# MAIN.net
KiCad netlist of a schematic drawn in Altium Designer
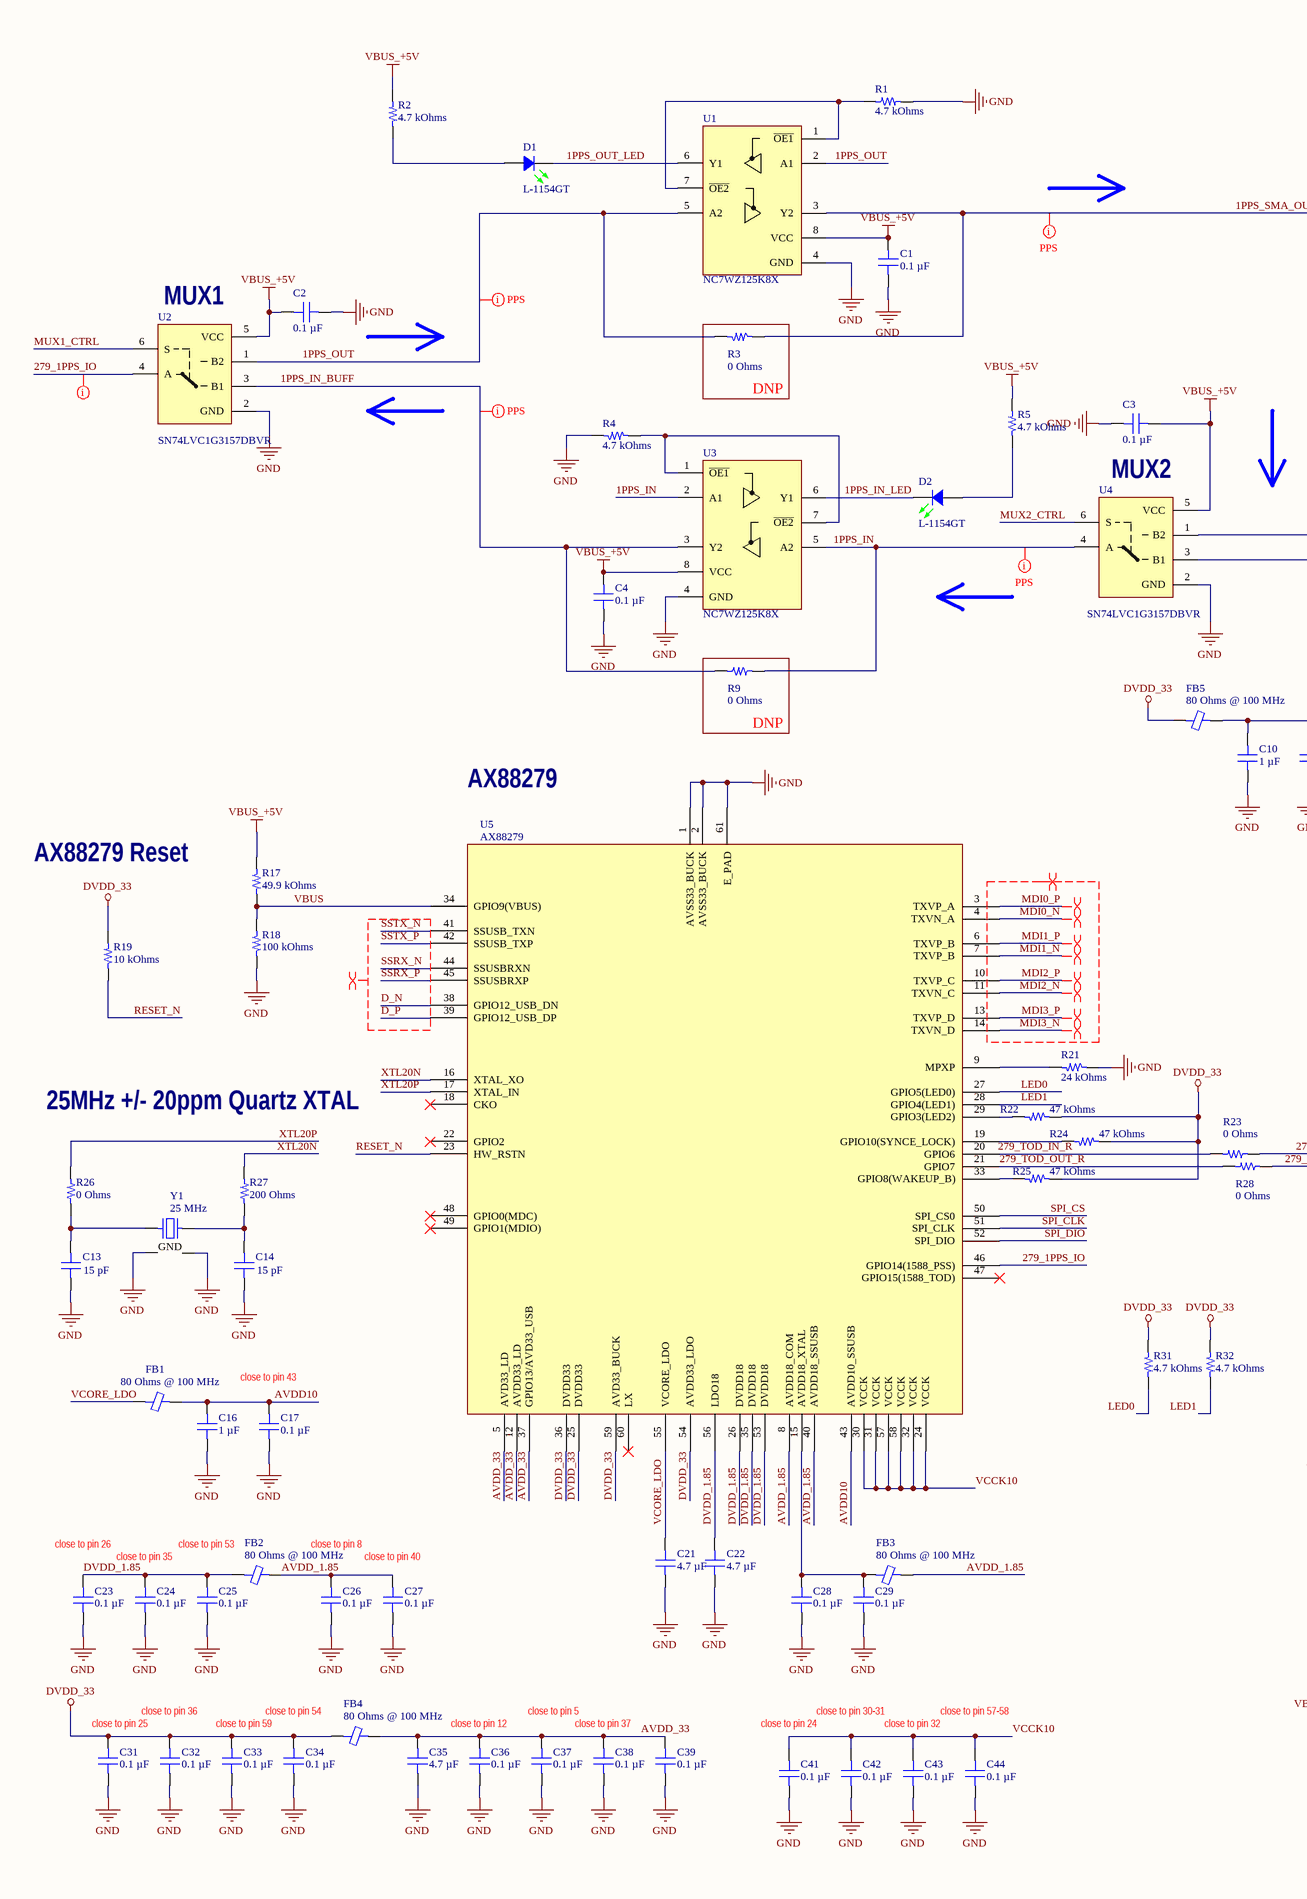
[diagram p0: MAIN.SchDoc, left]
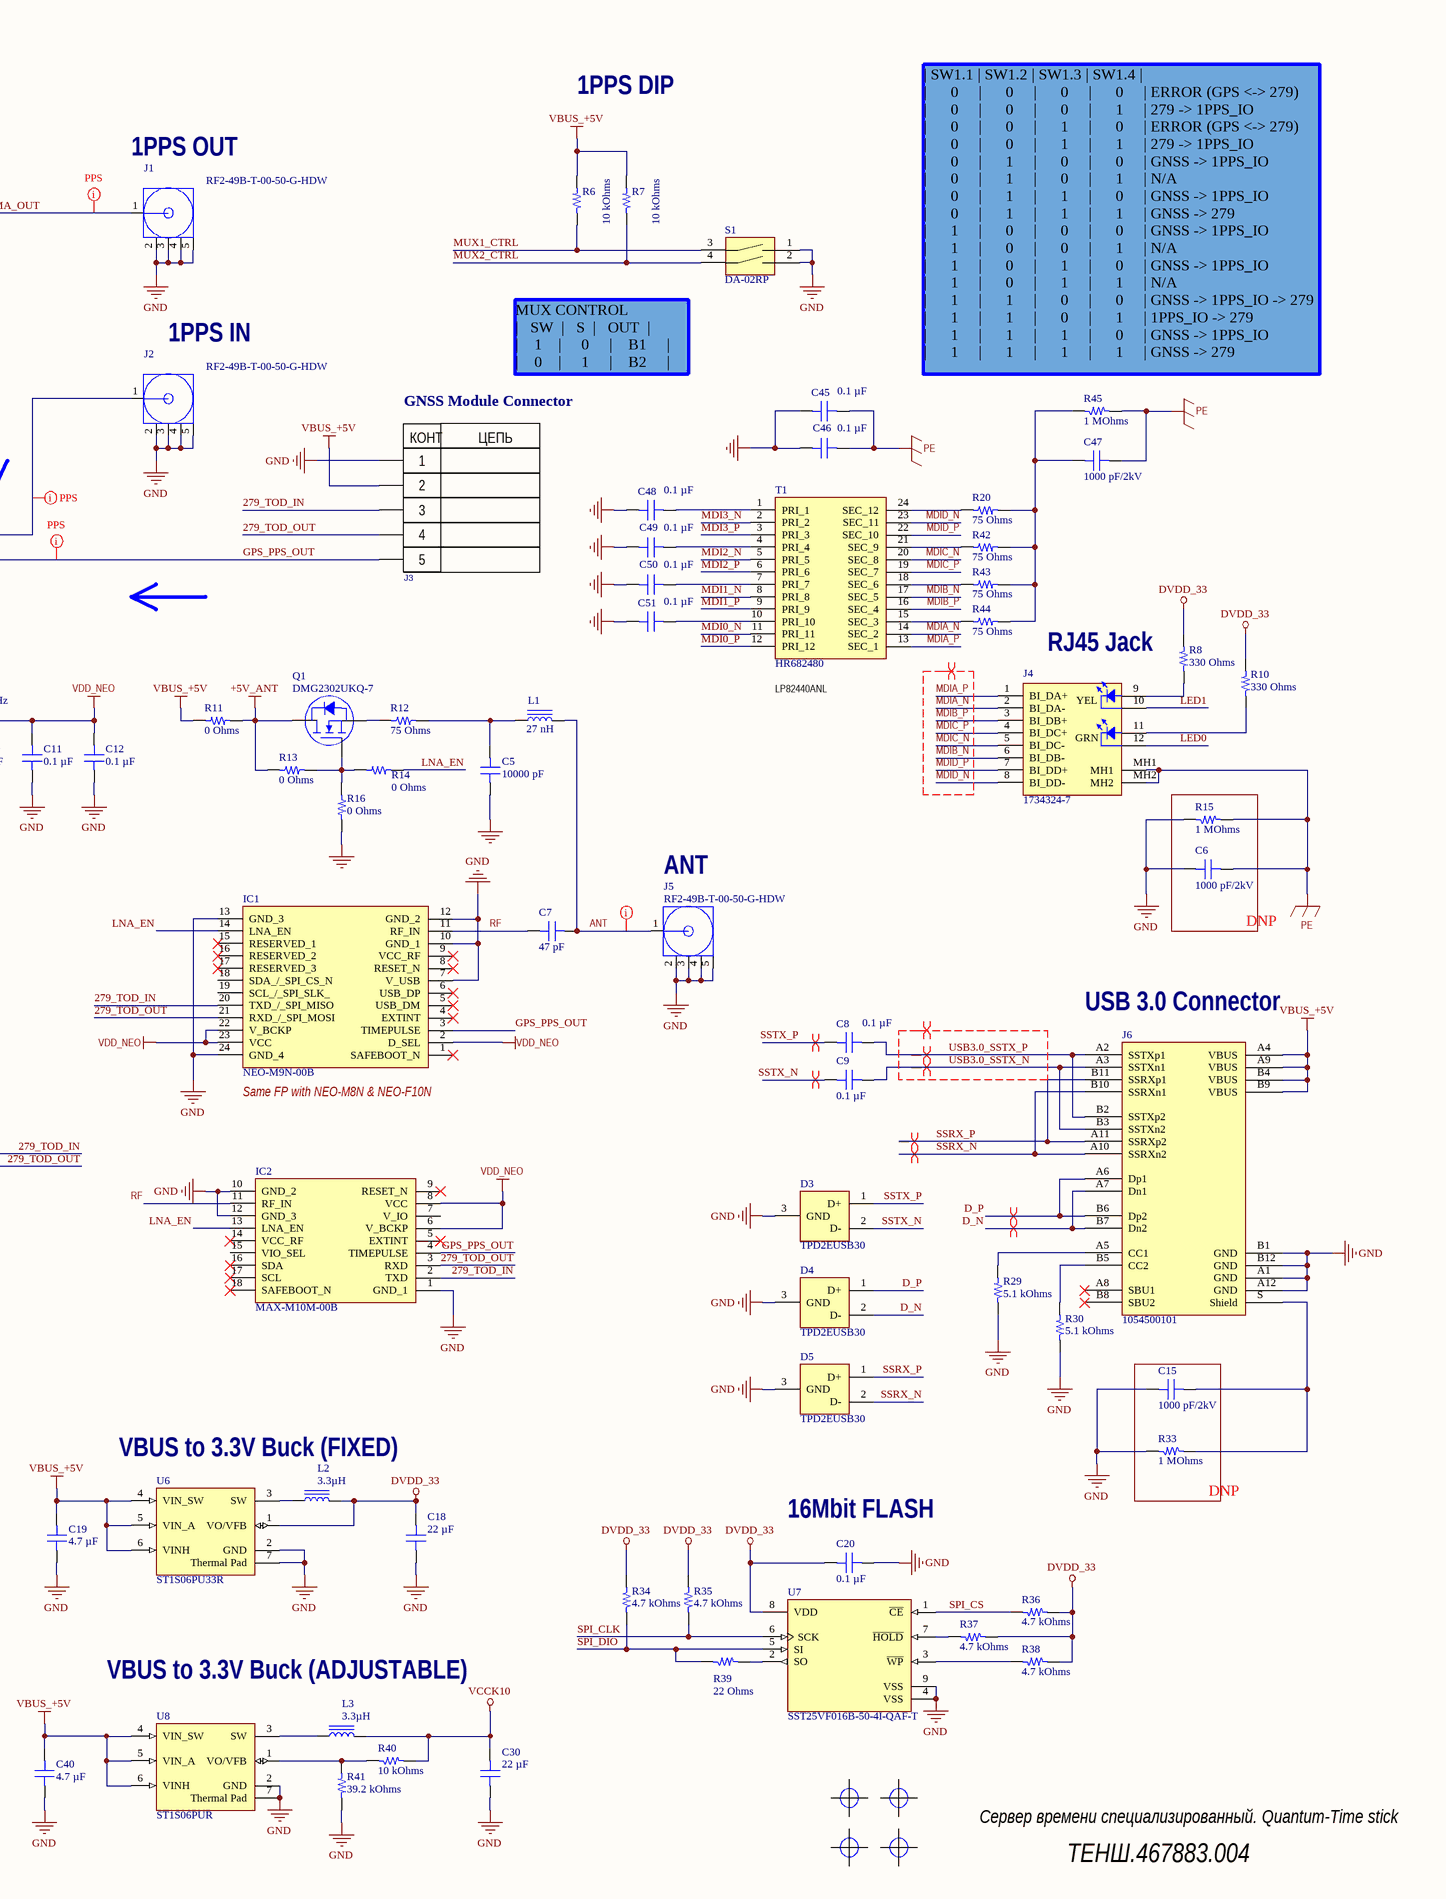
[diagram p1: MAIN.SchDoc, right]

(export (version "E")
  (design (tool "Eeschema 10.0.6"))
  (components
    (comp (ref "C1")
      (value "0.1 µF")
      (footprint "CAP 0402_1005")
      (description "CAP CER 0.1UF 10V X7R 0402")
      (fields (field (name "TOLERANCE") "±10%") (field (name "MANUFACTURER") "Yageo"))
      (libsource (lib "Celestial Altium Library - altium_library") (part "Capacitor"))
    )
    (comp (ref "C2")
      (value "0.1 µF")
      (footprint "CAP 0402_1005")
      (description "CAP CER 0.1UF 10V X7R 0402")
      (fields (field (name "TOLERANCE") "±10%") (field (name "MANUFACTURER") "Yageo"))
      (libsource (lib "Celestial Altium Library - altium_library") (part "Capacitor"))
    )
    (comp (ref "C3")
      (value "0.1 µF")
      (footprint "CAP 0402_1005")
      (description "CAP CER 0.1UF 10V X7R 0402")
      (fields (field (name "TOLERANCE") "±10%") (field (name "MANUFACTURER") "Yageo"))
      (libsource (lib "Celestial Altium Library - altium_library") (part "Capacitor"))
    )
    (comp (ref "C4")
      (value "0.1 µF")
      (footprint "CAP 0402_1005")
      (description "CAP CER 0.1UF 10V X7R 0402")
      (fields (field (name "TOLERANCE") "±10%") (field (name "MANUFACTURER") "Yageo"))
      (libsource (lib "Celestial Altium Library - altium_library") (part "Capacitor"))
    )
    (comp (ref "C5")
      (value "10000 pF")
      (footprint "CAP 0402_1005")
      (description "CAP CER 10000PF 50V X7R 0402")
      (fields (field (name "PART NUMBER") "CC0402KRX7R9BB103") (field (name "MANUFACTURER") "Yageo"))
      (libsource (lib "Celestial Altium Library - altium_library") (part "Capacitor"))
    )
    (comp (ref "C6")
      (value "1000 pF/2kV")
      (footprint "CAP 1206_3216 - 0.8MM")
      (description "CAP CER 1000PF 2KV X7R 1206")
      (fields (field (name "PART NUMBER") "CC1206KKX7RDBB102") (field (name "MANUFACTURER") "Yageo"))
      (libsource (lib "Celestial Altium Library - altium_library") (part "Capacitor"))
    )
    (comp (ref "C7")
      (value "47 pF")
      (footprint "CAP 0402_1005")
      (description "CAP CER 47PF 50V C0G/NPO 0402")
      (fields (field (name "MANUFACTURER") "Yageo") (field (name "TOLERANCE") "±10%"))
      (libsource (lib "Celestial Altium Library - altium_library") (part "Capacitor"))
    )
    (comp (ref "C8")
      (value "0.1 µF")
      (footprint "CAP 0402_1005")
      (description "CAP CER 0.1UF 10V X7R 0402")
      (fields (field (name "TOLERANCE") "±10%") (field (name "MANUFACTURER") "Yageo"))
      (libsource (lib "Celestial Altium Library - altium_library") (part "Capacitor"))
    )
    (comp (ref "C9")
      (value "0.1 µF")
      (footprint "CAP 0402_1005")
      (description "CAP CER 0.1UF 10V X7R 0402")
      (fields (field (name "TOLERANCE") "±10%") (field (name "MANUFACTURER") "Yageo"))
      (libsource (lib "Celestial Altium Library - altium_library") (part "Capacitor"))
    )
    (comp (ref "C10")
      (value "1 µF")
      (footprint "CAP 0402_1005")
      (description "CAP CER 1UF 10V X5R 0402")
      (fields (field (name "TOLERANCE") "±10%") (field (name "MANUFACTURER") "Yageo"))
      (libsource (lib "Celestial Altium Library - altium_library") (part "Capacitor"))
    )
    (comp (ref "C11")
      (value "0.1 µF")
      (footprint "CAP 0402_1005")
      (description "CAP CER 0.1UF 10V X7R 0402")
      (fields (field (name "TOLERANCE") "±10%") (field (name "MANUFACTURER") "Yageo"))
      (libsource (lib "Celestial Altium Library - altium_library") (part "Capacitor"))
    )
    (comp (ref "C12")
      (value "0.1 µF")
      (footprint "CAP 0402_1005")
      (description "CAP CER 0.1UF 10V X7R 0402")
      (fields (field (name "TOLERANCE") "±10%") (field (name "MANUFACTURER") "Yageo"))
      (libsource (lib "Celestial Altium Library - altium_library") (part "Capacitor"))
    )
    (comp (ref "C13")
      (value "15 pF")
      (footprint "CAP 0402_1005")
      (description "CAP CER 15PF 50V C0G/NPO 0402")
      (fields (field (name "MANUFACTURER") "Yageo") (field (name "TOLERANCE") "±10%"))
      (libsource (lib "Celestial Altium Library - altium_library") (part "Capacitor"))
    )
    (comp (ref "C14")
      (value "15 pF")
      (footprint "CAP 0402_1005")
      (description "CAP CER 15PF 50V C0G/NPO 0402")
      (fields (field (name "MANUFACTURER") "Yageo") (field (name "TOLERANCE") "±10%"))
      (libsource (lib "Celestial Altium Library - altium_library") (part "Capacitor"))
    )
    (comp (ref "C15")
      (value "1000 pF/2kV")
      (footprint "CAP 1206_3216 - 0.8MM")
      (description "CAP CER 1000PF 2KV X7R 1206")
      (fields (field (name "PART NUMBER") "CC1206KKX7RDBB102") (field (name "MANUFACTURER") "Yageo"))
      (libsource (lib "Celestial Altium Library - altium_library") (part "Capacitor"))
    )
    (comp (ref "C16")
      (value "1 µF")
      (footprint "CAP 0402_1005")
      (description "CAP CER 1UF 10V X5R 0402")
      (fields (field (name "TOLERANCE") "±10%") (field (name "MANUFACTURER") "Yageo"))
      (libsource (lib "Celestial Altium Library - altium_library") (part "Capacitor"))
    )
    (comp (ref "C17")
      (value "0.1 µF")
      (footprint "CAP 0402_1005")
      (description "CAP CER 0.1UF 10V X7R 0402")
      (fields (field (name "TOLERANCE") "±10%") (field (name "MANUFACTURER") "Yageo"))
      (libsource (lib "Celestial Altium Library - altium_library") (part "Capacitor"))
    )
    (comp (ref "C18")
      (value "22 µF")
      (footprint "CAP 0603_1608")
      (description "CAP CER 22UF 10V X5R 0603")
      (fields (field (name "MANUFACTURER") "Yageo") (field (name "TOLERANCE") "±20%"))
      (libsource (lib "Celestial Altium Library - altium_library") (part "Capacitor"))
    )
    (comp (ref "C19")
      (value "4.7 µF")
      (footprint "CAP 0402_1005")
      (description "CAP CER 4.7UF 10V X5R 0402")
      (fields (field (name "TOLERANCE") "±20%") (field (name "MANUFACTURER") "Yageo"))
      (libsource (lib "Celestial Altium Library - altium_library") (part "Capacitor"))
    )
    (comp (ref "C20")
      (value "0.1 µF")
      (footprint "CAP 0402_1005")
      (description "CAP CER 0.1UF 10V X7R 0402")
      (fields (field (name "TOLERANCE") "±10%") (field (name "MANUFACTURER") "Yageo"))
      (libsource (lib "Celestial Altium Library - altium_library") (part "Capacitor"))
    )
    (comp (ref "C21")
      (value "4.7 µF")
      (footprint "CAP 0402_1005")
      (description "CAP CER 4.7UF 10V X5R 0402")
      (fields (field (name "TOLERANCE") "±20%") (field (name "MANUFACTURER") "Yageo"))
      (libsource (lib "Celestial Altium Library - altium_library") (part "Capacitor"))
    )
    (comp (ref "C22")
      (value "4.7 µF")
      (footprint "CAP 0402_1005")
      (description "CAP CER 4.7UF 10V X5R 0402")
      (fields (field (name "TOLERANCE") "±20%") (field (name "MANUFACTURER") "Yageo"))
      (libsource (lib "Celestial Altium Library - altium_library") (part "Capacitor"))
    )
    (comp (ref "C23")
      (value "0.1 µF")
      (footprint "CAP 0402_1005")
      (description "CAP CER 0.1UF 10V X7R 0402")
      (fields (field (name "TOLERANCE") "±10%") (field (name "MANUFACTURER") "Yageo"))
      (libsource (lib "Celestial Altium Library - altium_library") (part "Capacitor"))
    )
    (comp (ref "C24")
      (value "0.1 µF")
      (footprint "CAP 0402_1005")
      (description "CAP CER 0.1UF 10V X7R 0402")
      (fields (field (name "TOLERANCE") "±10%") (field (name "MANUFACTURER") "Yageo"))
      (libsource (lib "Celestial Altium Library - altium_library") (part "Capacitor"))
    )
    (comp (ref "C25")
      (value "0.1 µF")
      (footprint "CAP 0402_1005")
      (description "CAP CER 0.1UF 10V X7R 0402")
      (fields (field (name "TOLERANCE") "±10%") (field (name "MANUFACTURER") "Yageo"))
      (libsource (lib "Celestial Altium Library - altium_library") (part "Capacitor"))
    )
    (comp (ref "C26")
      (value "0.1 µF")
      (footprint "CAP 0402_1005")
      (description "CAP CER 0.1UF 10V X7R 0402")
      (fields (field (name "TOLERANCE") "±10%") (field (name "MANUFACTURER") "Yageo"))
      (libsource (lib "Celestial Altium Library - altium_library") (part "Capacitor"))
    )
    (comp (ref "C27")
      (value "0.1 µF")
      (footprint "CAP 0402_1005")
      (description "CAP CER 0.1UF 10V X7R 0402")
      (fields (field (name "TOLERANCE") "±10%") (field (name "MANUFACTURER") "Yageo"))
      (libsource (lib "Celestial Altium Library - altium_library") (part "Capacitor"))
    )
    (comp (ref "C28")
      (value "0.1 µF")
      (footprint "CAP 0402_1005")
      (description "CAP CER 0.1UF 10V X7R 0402")
      (fields (field (name "TOLERANCE") "±10%") (field (name "MANUFACTURER") "Yageo"))
      (libsource (lib "Celestial Altium Library - altium_library") (part "Capacitor"))
    )
    (comp (ref "C29")
      (value "0.1 µF")
      (footprint "CAP 0402_1005")
      (description "CAP CER 0.1UF 10V X7R 0402")
      (fields (field (name "TOLERANCE") "±10%") (field (name "MANUFACTURER") "Yageo"))
      (libsource (lib "Celestial Altium Library - altium_library") (part "Capacitor"))
    )
    (comp (ref "C30")
      (value "22 µF")
      (footprint "CAP 0603_1608")
      (description "CAP CER 22UF 10V X5R 0603")
      (fields (field (name "MANUFACTURER") "Yageo") (field (name "TOLERANCE") "±20%"))
      (libsource (lib "Celestial Altium Library - altium_library") (part "Capacitor"))
    )
    (comp (ref "C31")
      (value "0.1 µF")
      (footprint "CAP 0402_1005")
      (description "CAP CER 0.1UF 10V X7R 0402")
      (fields (field (name "TOLERANCE") "±10%") (field (name "MANUFACTURER") "Yageo"))
      (libsource (lib "Celestial Altium Library - altium_library") (part "Capacitor"))
    )
    (comp (ref "C32")
      (value "0.1 µF")
      (footprint "CAP 0402_1005")
      (description "CAP CER 0.1UF 10V X7R 0402")
      (fields (field (name "TOLERANCE") "±10%") (field (name "MANUFACTURER") "Yageo"))
      (libsource (lib "Celestial Altium Library - altium_library") (part "Capacitor"))
    )
    (comp (ref "C33")
      (value "0.1 µF")
      (footprint "CAP 0402_1005")
      (description "CAP CER 0.1UF 10V X7R 0402")
      (fields (field (name "TOLERANCE") "±10%") (field (name "MANUFACTURER") "Yageo"))
      (libsource (lib "Celestial Altium Library - altium_library") (part "Capacitor"))
    )
    (comp (ref "C34")
      (value "0.1 µF")
      (footprint "CAP 0402_1005")
      (description "CAP CER 0.1UF 10V X7R 0402")
      (fields (field (name "TOLERANCE") "±10%") (field (name "MANUFACTURER") "Yageo"))
      (libsource (lib "Celestial Altium Library - altium_library") (part "Capacitor"))
    )
    (comp (ref "C35")
      (value "4.7 µF")
      (footprint "CAP 0402_1005")
      (description "CAP CER 4.7UF 10V X5R 0402")
      (fields (field (name "TOLERANCE") "±20%") (field (name "MANUFACTURER") "Yageo"))
      (libsource (lib "Celestial Altium Library - altium_library") (part "Capacitor"))
    )
    (comp (ref "C36")
      (value "0.1 µF")
      (footprint "CAP 0402_1005")
      (description "CAP CER 0.1UF 10V X7R 0402")
      (fields (field (name "TOLERANCE") "±10%") (field (name "MANUFACTURER") "Yageo"))
      (libsource (lib "Celestial Altium Library - altium_library") (part "Capacitor"))
    )
    (comp (ref "C37")
      (value "0.1 µF")
      (footprint "CAP 0402_1005")
      (description "CAP CER 0.1UF 10V X7R 0402")
      (fields (field (name "TOLERANCE") "±10%") (field (name "MANUFACTURER") "Yageo"))
      (libsource (lib "Celestial Altium Library - altium_library") (part "Capacitor"))
    )
    (comp (ref "C38")
      (value "0.1 µF")
      (footprint "CAP 0402_1005")
      (description "CAP CER 0.1UF 10V X7R 0402")
      (fields (field (name "TOLERANCE") "±10%") (field (name "MANUFACTURER") "Yageo"))
      (libsource (lib "Celestial Altium Library - altium_library") (part "Capacitor"))
    )
    (comp (ref "C39")
      (value "0.1 µF")
      (footprint "CAP 0402_1005")
      (description "CAP CER 0.1UF 10V X7R 0402")
      (fields (field (name "TOLERANCE") "±10%") (field (name "MANUFACTURER") "Yageo"))
      (libsource (lib "Celestial Altium Library - altium_library") (part "Capacitor"))
    )
    (comp (ref "C40")
      (value "4.7 µF")
      (footprint "CAP 0402_1005")
      (description "CAP CER 4.7UF 10V X5R 0402")
      (fields (field (name "TOLERANCE") "±20%") (field (name "MANUFACTURER") "Yageo"))
      (libsource (lib "Celestial Altium Library - altium_library") (part "Capacitor"))
    )
    (comp (ref "C41")
      (value "0.1 µF")
      (footprint "CAP 0402_1005")
      (description "CAP CER 0.1UF 10V X7R 0402")
      (fields (field (name "TOLERANCE") "±10%") (field (name "MANUFACTURER") "Yageo"))
      (libsource (lib "Celestial Altium Library - altium_library") (part "Capacitor"))
    )
    (comp (ref "C42")
      (value "0.1 µF")
      (footprint "CAP 0402_1005")
      (description "CAP CER 0.1UF 10V X7R 0402")
      (fields (field (name "TOLERANCE") "±10%") (field (name "MANUFACTURER") "Yageo"))
      (libsource (lib "Celestial Altium Library - altium_library") (part "Capacitor"))
    )
    (comp (ref "C43")
      (value "0.1 µF")
      (footprint "CAP 0402_1005")
      (description "CAP CER 0.1UF 10V X7R 0402")
      (fields (field (name "TOLERANCE") "±10%") (field (name "MANUFACTURER") "Yageo"))
      (libsource (lib "Celestial Altium Library - altium_library") (part "Capacitor"))
    )
    (comp (ref "C44")
      (value "0.1 µF")
      (footprint "CAP 0402_1005")
      (description "CAP CER 0.1UF 10V X7R 0402")
      (fields (field (name "TOLERANCE") "±10%") (field (name "MANUFACTURER") "Yageo"))
      (libsource (lib "Celestial Altium Library - altium_library") (part "Capacitor"))
    )
    (comp (ref "C45")
      (value "0.1 µF")
      (footprint "CAP 0402_1005")
      (description "CAP CER 0.1UF 10V X7R 0402")
      (fields (field (name "TOLERANCE") "±10%") (field (name "MANUFACTURER") "Yageo"))
      (libsource (lib "Celestial Altium Library - altium_library") (part "Capacitor"))
    )
    (comp (ref "C46")
      (value "0.1 µF")
      (footprint "CAP 0402_1005")
      (description "CAP CER 0.1UF 10V X7R 0402")
      (fields (field (name "TOLERANCE") "±10%") (field (name "MANUFACTURER") "Yageo"))
      (libsource (lib "Celestial Altium Library - altium_library") (part "Capacitor"))
    )
    (comp (ref "C47")
      (value "1000 pF/2kV")
      (footprint "CAP 1206_3216 - 0.8MM")
      (description "CAP CER 1000PF 2KV X7R 1206")
      (fields (field (name "PART NUMBER") "CC1206KKX7RDBB102") (field (name "MANUFACTURER") "Yageo"))
      (libsource (lib "Celestial Altium Library - altium_library") (part "Capacitor"))
    )
    (comp (ref "C48")
      (value "0.1 µF")
      (footprint "CAP 0402_1005")
      (description "CAP CER 0.1UF 10V X7R 0402")
      (fields (field (name "TOLERANCE") "±10%") (field (name "MANUFACTURER") "Yageo"))
      (libsource (lib "Celestial Altium Library - altium_library") (part "Capacitor"))
    )
    (comp (ref "C49")
      (value "0.1 µF")
      (footprint "CAP 0402_1005")
      (description "CAP CER 0.1UF 10V X7R 0402")
      (fields (field (name "TOLERANCE") "±10%") (field (name "MANUFACTURER") "Yageo"))
      (libsource (lib "Celestial Altium Library - altium_library") (part "Capacitor"))
    )
    (comp (ref "C50")
      (value "0.1 µF")
      (footprint "CAP 0402_1005")
      (description "CAP CER 0.1UF 10V X7R 0402")
      (fields (field (name "TOLERANCE") "±10%") (field (name "MANUFACTURER") "Yageo"))
      (libsource (lib "Celestial Altium Library - altium_library") (part "Capacitor"))
    )
    (comp (ref "C51")
      (value "0.1 µF")
      (footprint "CAP 0402_1005")
      (description "CAP CER 0.1UF 10V X7R 0402")
      (fields (field (name "TOLERANCE") "±10%") (field (name "MANUFACTURER") "Yageo"))
      (libsource (lib "Celestial Altium Library - altium_library") (part "Capacitor"))
    )
    (comp (ref "D1")
      (value "L-1154GT")
      (footprint "SamacSys:LED_3MM_GREEN")
      (description "LED, 3mm, Green")
      (libsource (lib "SamacSys") (part "L-1154GT"))
    )
    (comp (ref "D2")
      (value "L-1154GT")
      (footprint "SamacSys:LED_3MM_GREEN")
      (description "LED, 3mm, Green")
      (libsource (lib "SamacSys") (part "L-1154GT"))
    )
    (comp (ref "D3")
      (value "TPD2EUSB30")
      (footprint "SamacSys:SOT35P100X50-3N")
      (description "TVS DIODE 3.6VWM 8VC SOT3")
      (fields
        (field (name "MANUFACTURER_PART_NUMBER") "TPD2EUSB30ADRTR")
        (field (name "MOUSER PART NUMBER") "595-TPD2EUSB30ADRTR")
      )
      (libsource (lib "SamacSys") (part "TPD2EUSB30ADRTR"))
    )
    (comp (ref "D4")
      (value "TPD2EUSB30")
      (footprint "SamacSys:SOT35P100X50-3N")
      (description "TVS DIODE 3.6VWM 8VC SOT3")
      (fields
        (field (name "MANUFACTURER_PART_NUMBER") "TPD2EUSB30ADRTR")
        (field (name "MOUSER PART NUMBER") "595-TPD2EUSB30ADRTR")
      )
      (libsource (lib "SamacSys") (part "TPD2EUSB30ADRTR"))
    )
    (comp (ref "D5")
      (value "TPD2EUSB30")
      (footprint "SamacSys:SOT35P100X50-3N")
      (description "TVS DIODE 3.6VWM 8VC SOT3")
      (fields
        (field (name "MANUFACTURER_PART_NUMBER") "TPD2EUSB30ADRTR")
        (field (name "MOUSER PART NUMBER") "595-TPD2EUSB30ADRTR")
      )
      (libsource (lib "SamacSys") (part "TPD2EUSB30ADRTR"))
    )
    (comp (ref "FB1")
      (value "80 Ohms @ 100 MHz")
      (footprint "FER 0402_1005")
      (description "FERRITE BEAD 80 OHM 0402 1LN")
      (fields
        (field (name "MANUFACTURER") "Murata Electronics")
        (field (name "PART NUMBER") "BLM15PD800SN1D")
      )
      (libsource (lib "Celestial Altium Library - altium_library") (part "Ferrite Chip"))
    )
    (comp (ref "FB2")
      (value "80 Ohms @ 100 MHz")
      (footprint "FER 0402_1005")
      (description "FERRITE BEAD 80 OHM 0402 1LN")
      (fields
        (field (name "MANUFACTURER") "Murata Electronics")
        (field (name "PART NUMBER") "BLM15PD800SN1D")
      )
      (libsource (lib "Celestial Altium Library - altium_library") (part "Ferrite Chip"))
    )
    (comp (ref "FB3")
      (value "80 Ohms @ 100 MHz")
      (footprint "FER 0402_1005")
      (description "FERRITE BEAD 80 OHM 0402 1LN")
      (fields
        (field (name "MANUFACTURER") "Murata Electronics")
        (field (name "PART NUMBER") "BLM15PD800SN1D")
      )
      (libsource (lib "Celestial Altium Library - altium_library") (part "Ferrite Chip"))
    )
    (comp (ref "FB4")
      (value "80 Ohms @ 100 MHz")
      (footprint "FER 0402_1005")
      (description "FERRITE BEAD 80 OHM 0402 1LN")
      (fields
        (field (name "MANUFACTURER") "Murata Electronics")
        (field (name "PART NUMBER") "BLM15PD800SN1D")
      )
      (libsource (lib "Celestial Altium Library - altium_library") (part "Ferrite Chip"))
    )
    (comp (ref "FB5")
      (value "80 Ohms @ 100 MHz")
      (footprint "FER 0402_1005")
      (description "FERRITE BEAD 80 OHM 0402 1LN")
      (fields
        (field (name "MANUFACTURER") "Murata Electronics")
        (field (name "PART NUMBER") "BLM15PD800SN1D")
      )
      (libsource (lib "Celestial Altium Library - altium_library") (part "Ferrite Chip"))
    )
    (comp (ref "IC1")
      (value "NEO-M9N-00B")
      (footprint "SamacSys:NEOM9N00B")
      (description "Integrated Circuit")
      (fields (field (name "MOUSER PART NUMBER") "377-NEO-M9N-00B"))
      (libsource (lib "SamacSys") (part "NEO-M9N-00B"))
    )
    (comp (ref "IC2")
      (value "MAX-M10M-00B")
      (footprint "MAXM10M00B")
      (description "Integrated Circuit")
      (fields (field (name "MOUSER PART NUMBER") "377-MAX-M10M-00B"))
      (libsource (lib "SamacSys") (part "MAX-M10M-00B"))
    )
    (comp (ref "J1")
      (value "RF2-49B-T-00-50-G-HDW")
      (footprint "SamacSys:RF249BT0050GHDW")
      (description "Connector")
      (libsource (lib "SamacSys") (part "RF2-49B-T-00-50-G-HDW"))
    )
    (comp (ref "J2")
      (value "RF2-49B-T-00-50-G-HDW")
      (footprint "SamacSys:RF249BT0050GHDW")
      (description "Connector")
      (libsource (lib "SamacSys") (part "RF2-49B-T-00-50-G-HDW"))
    )
    (comp (ref "J3")
      (value "PBS-5")
      (footprint "SamacSys:PBS-5")
      (description "Connector")
      (fields (field (name "MANUFACTURER") "Connfly") (field (name "PART NUMBER") "PBD-5"))
      (libsource (lib "SamacSys") (part "PBS-5"))
    )
    (comp (ref "J4")
      (value "1734324-7")
      (footprint "SamacSys:17343247")
      (description "Connector, RJ-45, with LED, w/o Mag, RA")
      (fields (field (name "MOUSER PART NUMBER") "571-1734324-7"))
      (libsource (lib "SamacSys") (part "1734324-7"))
    )
    (comp (ref "J5")
      (value "RF2-49B-T-00-50-G-HDW")
      (footprint "SamacSys:RF249BT0050GHDW")
      (description "Connector")
      (libsource (lib "SamacSys") (part "RF2-49B-T-00-50-G-HDW"))
    )
    (comp (ref "J6")
      (value "1054500101")
      (footprint "Molex 1054500101")
      (description "CONN RCP USB3.1 TYPEC 24P SMD RA")
      (fields (field (name "MANUFACTURER") "Molex"))
      (libsource (lib "Celestial Altium Library - altium_library") (part "USB 3.0 Type C"))
    )
    (comp (ref "L1")
      (value "27 nH")
      (footprint "Murata LQG15 0402")
      (description "FIXED IND 27NH 350MA 0.46OHM SMD")
      (fields
        (field (name "PART NUMBER") "LQG15HS27NJ02D")
        (field (name "MANUFACTURER") "Murata Electronics")
      )
      (libsource (lib "Celestial Altium Library - altium_library") (part "Inductor"))
    )
    (comp (ref "L2")
      (value "3.3µH")
      (footprint "IND 1008_2520")
      (description "FIXED IND 3.3UH 1.2A 100 MOHM")
      (fields (field (name "TOLERANCE") "±20%") (field (name "MANUFACTURER") "Murata Electronics"))
      (libsource (lib "Celestial Altium Library - altium_library") (part "Inductor"))
    )
    (comp (ref "L3")
      (value "3.3µH")
      (footprint "IND 1008_2520")
      (description "FIXED IND 3.3UH 1.2A 100 MOHM")
      (fields (field (name "TOLERANCE") "±20%") (field (name "MANUFACTURER") "Murata Electronics"))
      (libsource (lib "Celestial Altium Library - altium_library") (part "Inductor"))
    )
    (comp (ref "MNT1")
      (value "MOUNT_HOLE")
      (footprint "SamacSys:MOUNT_3mm")
      (description "Mount hole")
      (libsource (lib "SamacSys") (part "MOUNT_HOLE"))
    )
    (comp (ref "MNT2")
      (value "MOUNT_HOLE")
      (footprint "SamacSys:MOUNT_3mm")
      (description "Mount hole")
      (libsource (lib "SamacSys") (part "MOUNT_HOLE"))
    )
    (comp (ref "MNT3")
      (value "MOUNT_HOLE")
      (footprint "SamacSys:MOUNT_3mm")
      (description "Mount hole")
      (libsource (lib "SamacSys") (part "MOUNT_HOLE"))
    )
    (comp (ref "MNT4")
      (value "MOUNT_HOLE")
      (footprint "SamacSys:MOUNT_3mm")
      (description "Mount hole")
      (libsource (lib "SamacSys") (part "MOUNT_HOLE"))
    )
    (comp (ref "Q1")
      (value "DMG2302UKQ-7")
      (footprint "DIODES SOT-23-3")
      (description "MOSFET BVDSS: 8V-24V SOT23 T&R 3")
      (fields (field (name "MANUFACTURER") "Diodes Incorporated"))
      (libsource (lib "Celestial Altium Library - altium_library") (part "DIODES INC MOSFET N-CH SOT-23-3"))
    )
    (comp (ref "R1")
      (value "4.7 kOhms")
      (footprint "YAGEO RES 0402_1005")
      (description "RES 4.7K OHM 1% 1/16W 0402")
      (fields (field (name "TOLERANCE") "±1%") (field (name "MANUFACTURER") "Yageo"))
      (libsource (lib "Celestial Altium Library - altium_library") (part "Resistor"))
    )
    (comp (ref "R2")
      (value "4.7 kOhms")
      (footprint "YAGEO RES 0402_1005")
      (description "RES 4.7K OHM 1% 1/16W 0402")
      (fields (field (name "TOLERANCE") "±1%") (field (name "MANUFACTURER") "Yageo"))
      (libsource (lib "Celestial Altium Library - altium_library") (part "Resistor"))
    )
    (comp (ref "R3")
      (value "0 Ohms")
      (footprint "YAGEO RES 0402_1005")
      (description "RES 0 OHM JUMPER 1/16W 0402")
      (fields (field (name "TOLERANCE") "Jumper") (field (name "MANUFACTURER") "Yageo"))
      (libsource (lib "Celestial Altium Library - altium_library") (part "Resistor"))
    )
    (comp (ref "R4")
      (value "4.7 kOhms")
      (footprint "YAGEO RES 0402_1005")
      (description "RES 4.7K OHM 1% 1/16W 0402")
      (fields (field (name "TOLERANCE") "±1%") (field (name "MANUFACTURER") "Yageo"))
      (libsource (lib "Celestial Altium Library - altium_library") (part "Resistor"))
    )
    (comp (ref "R5")
      (value "4.7 kOhms")
      (footprint "YAGEO RES 0402_1005")
      (description "RES 4.7K OHM 1% 1/16W 0402")
      (fields (field (name "TOLERANCE") "±1%") (field (name "MANUFACTURER") "Yageo"))
      (libsource (lib "Celestial Altium Library - altium_library") (part "Resistor"))
    )
    (comp (ref "R6")
      (value "10 kOhms")
      (footprint "YAGEO RES 0402_1005")
      (description "RES 10K OHM 1% 1/16W 0402")
      (fields (field (name "TOLERANCE") "±1%") (field (name "MANUFACTURER") "Yageo"))
      (libsource (lib "Celestial Altium Library - altium_library") (part "Resistor"))
    )
    (comp (ref "R7")
      (value "10 kOhms")
      (footprint "YAGEO RES 0402_1005")
      (description "RES 10K OHM 1% 1/16W 0402")
      (fields (field (name "TOLERANCE") "±1%") (field (name "MANUFACTURER") "Yageo"))
      (libsource (lib "Celestial Altium Library - altium_library") (part "Resistor"))
    )
    (comp (ref "R8")
      (value "330 Ohms")
      (footprint "YAGEO RES 0402_1005")
      (description "RES 330 OHM 1% 1/16W 0402")
      (fields (field (name "TOLERANCE") "±1%") (field (name "MANUFACTURER") "Yageo"))
      (libsource (lib "Celestial Altium Library - altium_library") (part "Resistor"))
    )
    (comp (ref "R9")
      (value "0 Ohms")
      (footprint "YAGEO RES 0402_1005")
      (description "RES 0 OHM JUMPER 1/16W 0402")
      (fields (field (name "TOLERANCE") "Jumper") (field (name "MANUFACTURER") "Yageo"))
      (libsource (lib "Celestial Altium Library - altium_library") (part "Resistor"))
    )
    (comp (ref "R10")
      (value "330 Ohms")
      (footprint "YAGEO RES 0402_1005")
      (description "RES 330 OHM 1% 1/16W 0402")
      (fields (field (name "TOLERANCE") "±1%") (field (name "MANUFACTURER") "Yageo"))
      (libsource (lib "Celestial Altium Library - altium_library") (part "Resistor"))
    )
    (comp (ref "R11")
      (value "0 Ohms")
      (footprint "YAGEO RES 0402_1005")
      (description "RES 0 OHM JUMPER 1/16W 0402")
      (fields (field (name "TOLERANCE") "Jumper") (field (name "MANUFACTURER") "Yageo"))
      (libsource (lib "Celestial Altium Library - altium_library") (part "Resistor"))
    )
    (comp (ref "R12")
      (value "75 Ohms")
      (footprint "YAGEO RES 0603_1608")
      (description "RES 75 OHM 1% 1/10W 0603")
      (fields (field (name "PART NUMBER") "RC0603FR-0775RL") (field (name "MANUFACTURER") "Yageo"))
      (libsource (lib "Celestial Altium Library - altium_library") (part "Resistor"))
    )
    (comp (ref "R13")
      (value "0 Ohms")
      (footprint "YAGEO RES 0402_1005")
      (description "RES 0 OHM JUMPER 1/16W 0402")
      (fields (field (name "TOLERANCE") "Jumper") (field (name "MANUFACTURER") "Yageo"))
      (libsource (lib "Celestial Altium Library - altium_library") (part "Resistor"))
    )
    (comp (ref "R14")
      (value "0 Ohms")
      (footprint "YAGEO RES 0402_1005")
      (description "RES 0 OHM JUMPER 1/16W 0402")
      (fields (field (name "TOLERANCE") "Jumper") (field (name "MANUFACTURER") "Yageo"))
      (libsource (lib "Celestial Altium Library - altium_library") (part "Resistor"))
    )
    (comp (ref "R15")
      (value "1 MOhms")
      (footprint "YAGEO RES 0402_1005")
      (description "RES 1M OHM 1% 1/16W 0402")
      (fields (field (name "TOLERANCE") "±1%") (field (name "MANUFACTURER") "Yageo"))
      (libsource (lib "Celestial Altium Library - altium_library") (part "Resistor"))
    )
    (comp (ref "R16")
      (value "0 Ohms")
      (footprint "YAGEO RES 0402_1005")
      (description "RES 0 OHM JUMPER 1/16W 0402")
      (fields (field (name "TOLERANCE") "Jumper") (field (name "MANUFACTURER") "Yageo"))
      (libsource (lib "Celestial Altium Library - altium_library") (part "Resistor"))
    )
    (comp (ref "R17")
      (value "49.9 kOhms")
      (footprint "YAGEO RES 0402_1005")
      (description "RES 49.9K OHM 1% 1/16W 0402")
      (fields (field (name "TOLERANCE") "±1%") (field (name "MANUFACTURER") "Yageo"))
      (libsource (lib "Celestial Altium Library - altium_library") (part "Resistor"))
    )
    (comp (ref "R18")
      (value "100 kOhms")
      (footprint "YAGEO RES 0402_1005")
      (description "RES 100K OHM 1% 1/16W 0402")
      (fields (field (name "TOLERANCE") "±1%") (field (name "MANUFACTURER") "Yageo"))
      (libsource (lib "Celestial Altium Library - altium_library") (part "Resistor"))
    )
    (comp (ref "R19")
      (value "10 kOhms")
      (footprint "YAGEO RES 0402_1005")
      (description "RES 10K OHM 1% 1/16W 0402")
      (fields (field (name "TOLERANCE") "±1%") (field (name "MANUFACTURER") "Yageo"))
      (libsource (lib "Celestial Altium Library - altium_library") (part "Resistor"))
    )
    (comp (ref "R20")
      (value "75 Ohms")
      (footprint "YAGEO RES 0603_1608")
      (description "RES 75 OHM 1% 1/10W 0603")
      (fields (field (name "PART NUMBER") "RC0603FR-0775RL") (field (name "MANUFACTURER") "Yageo"))
      (libsource (lib "Celestial Altium Library - altium_library") (part "Resistor"))
    )
    (comp (ref "R21")
      (value "24 kOhms")
      (footprint "YAGEO RES 0402_1005")
      (description "RES 24K OHM 1% 1/16W 0402")
      (fields (field (name "TOLERANCE") "±1%") (field (name "MANUFACTURER") "Yageo"))
      (libsource (lib "Celestial Altium Library - altium_library") (part "Resistor"))
    )
    (comp (ref "R22")
      (value "47 kOhms")
      (footprint "YAGEO RES 0402_1005")
      (description "RES 47K OHM 1% 1/16W 0402")
      (fields (field (name "TOLERANCE") "±1%") (field (name "MANUFACTURER") "Yageo"))
      (libsource (lib "Celestial Altium Library - altium_library") (part "Resistor"))
    )
    (comp (ref "R23")
      (value "0 Ohms")
      (footprint "YAGEO RES 0402_1005")
      (description "RES 0 OHM JUMPER 1/16W 0402")
      (fields (field (name "TOLERANCE") "Jumper") (field (name "MANUFACTURER") "Yageo"))
      (libsource (lib "Celestial Altium Library - altium_library") (part "Resistor"))
    )
    (comp (ref "R24")
      (value "47 kOhms")
      (footprint "YAGEO RES 0402_1005")
      (description "RES 47K OHM 1% 1/16W 0402")
      (fields (field (name "TOLERANCE") "±1%") (field (name "MANUFACTURER") "Yageo"))
      (libsource (lib "Celestial Altium Library - altium_library") (part "Resistor"))
    )
    (comp (ref "R25")
      (value "47 kOhms")
      (footprint "YAGEO RES 0402_1005")
      (description "RES 47K OHM 1% 1/16W 0402")
      (fields (field (name "TOLERANCE") "±1%") (field (name "MANUFACTURER") "Yageo"))
      (libsource (lib "Celestial Altium Library - altium_library") (part "Resistor"))
    )
    (comp (ref "R26")
      (value "0 Ohms")
      (footprint "YAGEO RES 0402_1005")
      (description "RES 0 OHM JUMPER 1/16W 0402")
      (fields (field (name "TOLERANCE") "Jumper") (field (name "MANUFACTURER") "Yageo"))
      (libsource (lib "Celestial Altium Library - altium_library") (part "Resistor"))
    )
    (comp (ref "R27")
      (value "200 Ohms")
      (footprint "YAGEO RES 0402_1005")
      (description "RES 200 OHM 1% 1/16W 0402")
      (fields (field (name "MANUFACTURER") "Yageo") (field (name "PART NUMBER") "RC0402FR-07200RL"))
      (libsource (lib "Celestial Altium Library - altium_library") (part "Resistor"))
    )
    (comp (ref "R28")
      (value "0 Ohms")
      (footprint "YAGEO RES 0402_1005")
      (description "RES 0 OHM JUMPER 1/16W 0402")
      (fields (field (name "TOLERANCE") "Jumper") (field (name "MANUFACTURER") "Yageo"))
      (libsource (lib "Celestial Altium Library - altium_library") (part "Resistor"))
    )
    (comp (ref "R29")
      (value "5.1 kOhms")
      (footprint "YAGEO RES 0402_1005")
      (description "RES 5.1K OHM 1% 1/16W 0402")
      (fields (field (name "TOLERANCE") "±1%") (field (name "MANUFACTURER") "Yageo"))
      (libsource (lib "Celestial Altium Library - altium_library") (part "Resistor"))
    )
    (comp (ref "R30")
      (value "5.1 kOhms")
      (footprint "YAGEO RES 0402_1005")
      (description "RES 5.1K OHM 1% 1/16W 0402")
      (fields (field (name "TOLERANCE") "±1%") (field (name "MANUFACTURER") "Yageo"))
      (libsource (lib "Celestial Altium Library - altium_library") (part "Resistor"))
    )
    (comp (ref "R31")
      (value "4.7 kOhms")
      (footprint "YAGEO RES 0402_1005")
      (description "RES 4.7K OHM 1% 1/16W 0402")
      (fields (field (name "TOLERANCE") "±1%") (field (name "MANUFACTURER") "Yageo"))
      (libsource (lib "Celestial Altium Library - altium_library") (part "Resistor"))
    )
    (comp (ref "R32")
      (value "4.7 kOhms")
      (footprint "YAGEO RES 0402_1005")
      (description "RES 4.7K OHM 1% 1/16W 0402")
      (fields (field (name "TOLERANCE") "±1%") (field (name "MANUFACTURER") "Yageo"))
      (libsource (lib "Celestial Altium Library - altium_library") (part "Resistor"))
    )
    (comp (ref "R33")
      (value "1 MOhms")
      (footprint "YAGEO RES 0402_1005")
      (description "RES 1M OHM 1% 1/16W 0402")
      (fields (field (name "TOLERANCE") "±1%") (field (name "MANUFACTURER") "Yageo"))
      (libsource (lib "Celestial Altium Library - altium_library") (part "Resistor"))
    )
    (comp (ref "R34")
      (value "4.7 kOhms")
      (footprint "YAGEO RES 0402_1005")
      (description "RES 4.7K OHM 1% 1/16W 0402")
      (fields (field (name "TOLERANCE") "±1%") (field (name "MANUFACTURER") "Yageo"))
      (libsource (lib "Celestial Altium Library - altium_library") (part "Resistor"))
    )
    (comp (ref "R35")
      (value "4.7 kOhms")
      (footprint "YAGEO RES 0402_1005")
      (description "RES 4.7K OHM 1% 1/16W 0402")
      (fields (field (name "TOLERANCE") "±1%") (field (name "MANUFACTURER") "Yageo"))
      (libsource (lib "Celestial Altium Library - altium_library") (part "Resistor"))
    )
    (comp (ref "R36")
      (value "4.7 kOhms")
      (footprint "YAGEO RES 0402_1005")
      (description "RES 4.7K OHM 1% 1/16W 0402")
      (fields (field (name "TOLERANCE") "±1%") (field (name "MANUFACTURER") "Yageo"))
      (libsource (lib "Celestial Altium Library - altium_library") (part "Resistor"))
    )
    (comp (ref "R37")
      (value "4.7 kOhms")
      (footprint "YAGEO RES 0402_1005")
      (description "RES 4.7K OHM 1% 1/16W 0402")
      (fields (field (name "TOLERANCE") "±1%") (field (name "MANUFACTURER") "Yageo"))
      (libsource (lib "Celestial Altium Library - altium_library") (part "Resistor"))
    )
    (comp (ref "R38")
      (value "4.7 kOhms")
      (footprint "YAGEO RES 0402_1005")
      (description "RES 4.7K OHM 1% 1/16W 0402")
      (fields (field (name "TOLERANCE") "±1%") (field (name "MANUFACTURER") "Yageo"))
      (libsource (lib "Celestial Altium Library - altium_library") (part "Resistor"))
    )
    (comp (ref "R39")
      (value "22 Ohms")
      (footprint "YAGEO RES 0402_1005")
      (description "RES 22 OHM 1% 1/16W 0402")
      (fields (field (name "TOLERANCE") "±1%") (field (name "MANUFACTURER") "Yageo"))
      (libsource (lib "Celestial Altium Library - altium_library") (part "Resistor"))
    )
    (comp (ref "R40")
      (value "10 kOhms")
      (footprint "YAGEO RES 0402_1005")
      (description "RES 10K OHM 1% 1/16W 0402")
      (fields (field (name "TOLERANCE") "±1%") (field (name "MANUFACTURER") "Yageo"))
      (libsource (lib "Celestial Altium Library - altium_library") (part "Resistor"))
    )
    (comp (ref "R41")
      (value "39.2 kOhms")
      (footprint "YAGEO RES 0402_1005")
      (description "RES 39.2K OHM 1% 1/16W 0402")
      (fields (field (name "TOLERANCE") "±1%") (field (name "MANUFACTURER") "Yageo"))
      (libsource (lib "Celestial Altium Library - altium_library") (part "Resistor"))
    )
    (comp (ref "R42")
      (value "75 Ohms")
      (footprint "YAGEO RES 0603_1608")
      (description "RES 75 OHM 1% 1/10W 0603")
      (fields (field (name "PART NUMBER") "RC0603FR-0775RL") (field (name "MANUFACTURER") "Yageo"))
      (libsource (lib "Celestial Altium Library - altium_library") (part "Resistor"))
    )
    (comp (ref "R43")
      (value "75 Ohms")
      (footprint "YAGEO RES 0603_1608")
      (description "RES 75 OHM 1% 1/10W 0603")
      (fields (field (name "PART NUMBER") "RC0603FR-0775RL") (field (name "MANUFACTURER") "Yageo"))
      (libsource (lib "Celestial Altium Library - altium_library") (part "Resistor"))
    )
    (comp (ref "R44")
      (value "75 Ohms")
      (footprint "YAGEO RES 0603_1608")
      (description "RES 75 OHM 1% 1/10W 0603")
      (fields (field (name "PART NUMBER") "RC0603FR-0775RL") (field (name "MANUFACTURER") "Yageo"))
      (libsource (lib "Celestial Altium Library - altium_library") (part "Resistor"))
    )
    (comp (ref "R45")
      (value "1 MOhms")
      (footprint "YAGEO RES 0402_1005")
      (description "RES 1M OHM 1% 1/16W 0402")
      (fields (field (name "TOLERANCE") "±1%") (field (name "MANUFACTURER") "Yageo"))
      (libsource (lib "Celestial Altium Library - altium_library") (part "Resistor"))
    )
    (comp (ref "S1")
      (value "DA-02RP")
      (footprint "SamacSys:DA02RP")
      (description "DIP Switch, 2P")
      (libsource (lib "SamacSys") (part "DA-02RP"))
    )
    (comp (ref "T1")
      (value "HR682480")
      (footprint "SamacSys:SOP99P1016X432-24N")
      (description "Transformer")
      (fields (field (name "PART NUMBER") "LP82440ANL"))
      (libsource (lib "SamacSys") (part "HR682480"))
    )
    (comp (ref "U1")
      (value "NC7WZ125K8X")
      (footprint "SamacSys:SOP50P310X90-8N")
      (description "Integrated Circuit")
      (libsource (lib "") (part "NC7WZ125K8X_1"))
    )
    (comp (ref "U2")
      (value "SN74LVC1G3157DBVR")
      (footprint "SamacSys:SOT95P280X145-6N")
      (description "Integrated Circuit")
      (fields (field (name "MOUSER PART NUMBER") "595-SN74LVC1G3157DBV"))
      (libsource (lib "SamacSys") (part "SN74LVC1G3157DBVR"))
    )
    (comp (ref "U3")
      (value "NC7WZ125K8X")
      (footprint "SamacSys:SOP50P310X90-8N")
      (description "Integrated Circuit")
      (libsource (lib "SamacSys") (part "NC7WZ125K8X"))
    )
    (comp (ref "U4")
      (value "SN74LVC1G3157DBVR")
      (footprint "SamacSys:SOT95P280X145-6N")
      (description "Integrated Circuit")
      (fields (field (name "MOUSER PART NUMBER") "595-SN74LVC1G3157DBV"))
      (libsource (lib "SamacSys") (part "SN74LVC1G3157DBVR"))
    )
    (comp (ref "U5")
      (value "AX88279")
      (footprint "IC_AX88279")
      (libsource (lib "LotusSound") (part "IC_AX88279"))
    )
    (comp (ref "U6")
      (value "ST1S06PU33R")
      (footprint "DFN6D_L")
      (fields (field (name "MANUFACTURER") "STMicroelectronics"))
      (libsource (lib "Altium Content Vault") (part "PM-DCDC-ST1S06-IL7"))
    )
    (comp (ref "U7")
      (value "SST25VF016B-50-4I-QAF-T")
      (footprint "FP-C04-452-MFG")
      (libsource (lib "Altium Content Vault") (part "d7313dde12fd16fde488169701056cc"))
    )
    (comp (ref "U8")
      (value "ST1S06PUR")
      (footprint "DFN6D_M")
      (libsource (lib "Altium Content Vault") (part "PM-DCDC-ST1S06-IL7"))
    )
    (comp (ref "Y1")
      (value "25 MHz")
      (footprint "NDK NX3225GA")
      (description "CRYSTAL 25.0000MHZ 8PF SMD")
      (fields
        (field (name "MANUFACTURER") "NDK America, Inc.")
        (field (name "PART NUMBER") "NX3225GA-25.000M-STD-CRG-2")
      )
      (libsource (lib "Celestial Altium Library - altium_library") (part "NDK Crystal NX3225GA"))
    )
  )
  (nets
    (net (code "1") (name "+5V_ANT") (class "Default")
      (node (ref "Q1") (pin "3") (pinfunction "D_3") (pintype "passive"))
      (node (ref "R11") (pin "1") (pinfunction "1_1") (pintype "passive"))
      (node (ref "R13") (pin "2") (pinfunction "2_2") (pintype "passive"))
    )
    (net (code "2") (name "/1PPS_IN") (class "Default")
      (node (ref "R9") (pin "1") (pinfunction "1_1") (pintype "passive"))
      (node (ref "U3") (pin "2") (pinfunction "A1_2") (pintype "passive"))
      (node (ref "U3") (pin "5") (pinfunction "A2_5") (pintype "passive"))
      (node (ref "U4") (pin "4") (pinfunction "A_4") (pintype "passive"))
    )
    (net (code "3") (name "/1PPS_IN_BUFF") (class "Default")
      (node (ref "R9") (pin "2") (pinfunction "2_2") (pintype "passive"))
      (node (ref "U2") (pin "3") (pinfunction "B1_3") (pintype "passive"))
      (node (ref "U3") (pin "3") (pinfunction "Y2_3") (pintype "passive"))
    )
    (net (code "4") (name "/1PPS_IN_LED") (class "Default")
      (node (ref "D2") (pin "C") (pinfunction "C_C") (pintype "passive"))
      (node (ref "U3") (pin "6") (pinfunction "Y1_6") (pintype "passive"))
    )
    (net (code "5") (name "/1PPS_OUT") (class "Default")
      (node (ref "R3") (pin "2") (pinfunction "2_2") (pintype "passive"))
      (node (ref "U1") (pin "2") (pinfunction "A1_2") (pintype "passive"))
      (node (ref "U1") (pin "5") (pinfunction "A2_5") (pintype "passive"))
      (node (ref "U2") (pin "1") (pinfunction "B2_1") (pintype "passive"))
    )
    (net (code "6") (name "/1PPS_OUT_LED") (class "Default")
      (node (ref "D1") (pin "C") (pinfunction "C_C") (pintype "passive"))
      (node (ref "U1") (pin "6") (pinfunction "Y1_6") (pintype "passive"))
    )
    (net (code "7") (name "/1PPS_SMA_OUT") (class "Default")
      (node (ref "J1") (pin "1") (pinfunction "1_1") (pintype "passive"))
      (node (ref "R3") (pin "1") (pinfunction "1_1") (pintype "passive"))
      (node (ref "U1") (pin "3") (pinfunction "Y2_3") (pintype "passive"))
    )
    (net (code "8") (name "/279_1PPS_IO") (class "Default")
      (node (ref "U2") (pin "4") (pinfunction "A_4") (pintype "passive"))
      (node (ref "U5") (pin "46") (pinfunction "GPIO14(1588_PSS)_46") (pintype "passive"))
    )
    (net (code "9") (name "/279_TOD_IN") (class "Default")
      (node (ref "IC1") (pin "20") (pinfunction "TXD_/_SPI_MISO_20") (pintype "passive"))
      (node (ref "IC2") (pin "2") (pinfunction "TXD_2") (pintype "passive"))
      (node (ref "J3") (pin "3") (pinfunction "3_3") (pintype "passive"))
      (node (ref "R23") (pin "1") (pinfunction "1_1") (pintype "passive"))
    )
    (net (code "10") (name "/279_TOD_IN_R") (class "Default")
      (node (ref "R23") (pin "2") (pinfunction "2_2") (pintype "passive"))
      (node (ref "U5") (pin "20") (pinfunction "GPIO6_20") (pintype "passive"))
    )
    (net (code "11") (name "/279_TOD_OUT") (class "Default")
      (node (ref "IC1") (pin "21") (pinfunction "RXD_/_SPI_MOSI_21") (pintype "passive"))
      (node (ref "IC2") (pin "3") (pinfunction "RXD_3") (pintype "passive"))
      (node (ref "J3") (pin "4") (pinfunction "4_4") (pintype "passive"))
      (node (ref "R28") (pin "1") (pinfunction "1_1") (pintype "passive"))
    )
    (net (code "12") (name "/279_TOD_OUT_R") (class "Default")
      (node (ref "R28") (pin "2") (pinfunction "2_2") (pintype "passive"))
      (node (ref "U5") (pin "21") (pinfunction "GPIO7_21") (pintype "passive"))
    )
    (net (code "13") (name "/ANT") (class "Default")
      (node (ref "C7") (pin "1") (pinfunction "1_1") (pintype "passive"))
      (node (ref "J5") (pin "1") (pinfunction "1_1") (pintype "passive"))
      (node (ref "L1") (pin "2") (pinfunction "2_2") (pintype "passive"))
    )
    (net (code "14") (name "/AVDD10") (class "Default")
      (node (ref "C16") (pin "2") (pinfunction "2_2") (pintype "passive"))
      (node (ref "C17") (pin "2") (pinfunction "2_2") (pintype "passive"))
      (node (ref "FB1") (pin "2") (pinfunction "2_2") (pintype "passive"))
      (node (ref "U5") (pin "43") (pinfunction "AVDD10_SSUSB_43") (pintype "passive"))
    )
    (net (code "15") (name "/AVDD_1.85") (class "Default")
      (node (ref "C26") (pin "2") (pinfunction "2_2") (pintype "passive"))
      (node (ref "C27") (pin "2") (pinfunction "2_2") (pintype "passive"))
      (node (ref "FB2") (pin "2") (pinfunction "2_2") (pintype "passive"))
      (node (ref "FB3") (pin "2") (pinfunction "2_2") (pintype "passive"))
      (node (ref "U5") (pin "40") (pinfunction "AVDD18_SSUSB_40") (pintype "passive"))
      (node (ref "U5") (pin "8") (pinfunction "AVDD18_COM_8") (pintype "passive"))
    )
    (net (code "16") (name "/AVDD_33") (class "Default")
      (node (ref "C35") (pin "2") (pinfunction "2_2") (pintype "passive"))
      (node (ref "C36") (pin "2") (pinfunction "2_2") (pintype "passive"))
      (node (ref "C37") (pin "2") (pinfunction "2_2") (pintype "passive"))
      (node (ref "C38") (pin "2") (pinfunction "2_2") (pintype "passive"))
      (node (ref "C39") (pin "2") (pinfunction "2_2") (pintype "passive"))
      (node (ref "FB4") (pin "2") (pinfunction "2_2") (pintype "passive"))
      (node (ref "U5") (pin "12") (pinfunction "AVDD33_LD_12") (pintype "passive"))
      (node (ref "U5") (pin "37") (pinfunction "GPIO13/AVD33_USB_37") (pintype "passive"))
      (node (ref "U5") (pin "5") (pinfunction "AVD33_LD_5") (pintype "passive"))
    )
    (net (code "17") (name "/DVDD_1.85") (class "Default")
      (node (ref "C22") (pin "2") (pinfunction "2_2") (pintype "passive"))
      (node (ref "C23") (pin "2") (pinfunction "2_2") (pintype "passive"))
      (node (ref "C24") (pin "2") (pinfunction "2_2") (pintype "passive"))
      (node (ref "C25") (pin "2") (pinfunction "2_2") (pintype "passive"))
      (node (ref "FB2") (pin "1") (pinfunction "1_1") (pintype "passive"))
      (node (ref "U5") (pin "26") (pinfunction "DVDD18_26") (pintype "passive"))
      (node (ref "U5") (pin "35") (pinfunction "DVDD18_35") (pintype "passive"))
      (node (ref "U5") (pin "53") (pinfunction "DVDD18_53") (pintype "passive"))
      (node (ref "U5") (pin "56") (pinfunction "LDO18_56") (pintype "passive"))
    )
    (net (code "18") (name "/D_N") (class "Default")
      (node (ref "D4") (pin "2") (pinfunction "D-_2") (pintype "passive"))
      (node (ref "J6") (pin "A7") (pinfunction "Dn1_A7") (pintype "passive"))
      (node (ref "J6") (pin "B7") (pinfunction "Dn2_B7") (pintype "passive"))
      (node (ref "U5") (pin "38") (pinfunction "GPIO12_USB_DN_38") (pintype "passive"))
    )
    (net (code "19") (name "/D_P") (class "Default")
      (node (ref "D4") (pin "1") (pinfunction "D+_1") (pintype "passive"))
      (node (ref "J6") (pin "A6") (pinfunction "Dp1_A6") (pintype "passive"))
      (node (ref "J6") (pin "B6") (pinfunction "Dp2_B6") (pintype "passive"))
      (node (ref "U5") (pin "39") (pinfunction "GPIO12_USB_DP_39") (pintype "passive"))
    )
    (net (code "20") (name "/GPS_PPS_OUT") (class "Default")
      (node (ref "IC1") (pin "3") (pinfunction "TIMEPULSE_3") (pintype "passive"))
      (node (ref "IC2") (pin "4") (pinfunction "TIMEPULSE_4") (pintype "passive"))
      (node (ref "J3") (pin "5") (pinfunction "5_5") (pintype "passive"))
      (node (ref "U4") (pin "3") (pinfunction "B1_3") (pintype "passive"))
    )
    (net (code "21") (name "/LED0") (class "Default")
      (node (ref "J4") (pin "12") (pinfunction "K_GR_12") (pintype "passive"))
      (node (ref "R31") (pin "2") (pinfunction "2_2") (pintype "passive"))
      (node (ref "U5") (pin "27") (pinfunction "GPIO5(LED0)_27") (pintype "passive"))
    )
    (net (code "22") (name "/LED1") (class "Default")
      (node (ref "J4") (pin "10") (pinfunction "K_YEL_10") (pintype "passive"))
      (node (ref "R32") (pin "2") (pinfunction "2_2") (pintype "passive"))
      (node (ref "U5") (pin "28") (pinfunction "GPIO4(LED1)_28") (pintype "passive"))
    )
    (net (code "23") (name "/LNA_EN") (class "Default")
      (node (ref "IC1") (pin "14") (pinfunction "LNA_EN_14") (pintype "passive"))
      (node (ref "IC2") (pin "13") (pinfunction "LNA_EN_13") (pintype "passive"))
      (node (ref "R14") (pin "1") (pinfunction "1_1") (pintype "passive"))
    )
    (net (code "24") (name "/MDI0_N") (class "Default")
      (node (ref "T1") (pin "11") (pinfunction "PRI_11_11") (pintype "passive"))
      (node (ref "U5") (pin "4") (pinfunction "TXVN_A_4") (pintype "passive"))
    )
    (net (code "25") (name "/MDI0_P") (class "Default")
      (node (ref "T1") (pin "12") (pinfunction "PRI_12_12") (pintype "passive"))
      (node (ref "U5") (pin "3") (pinfunction "TXVP_A_3") (pintype "passive"))
    )
    (net (code "26") (name "/MDI1_N") (class "Default")
      (node (ref "T1") (pin "8") (pinfunction "PRI_8_8") (pintype "passive"))
      (node (ref "U5") (pin "7") (pinfunction "TXVP_B_7") (pintype "passive"))
    )
    (net (code "27") (name "/MDI1_P") (class "Default")
      (node (ref "T1") (pin "9") (pinfunction "PRI_9_9") (pintype "passive"))
      (node (ref "U5") (pin "6") (pinfunction "TXVP_B_6") (pintype "passive"))
    )
    (net (code "28") (name "/MDI2_N") (class "Default")
      (node (ref "T1") (pin "5") (pinfunction "PRI_5_5") (pintype "passive"))
      (node (ref "U5") (pin "11") (pinfunction "TXVN_C_11") (pintype "passive"))
    )
    (net (code "29") (name "/MDI2_P") (class "Default")
      (node (ref "T1") (pin "6") (pinfunction "PRI_6_6") (pintype "passive"))
      (node (ref "U5") (pin "10") (pinfunction "TXVP_C_10") (pintype "passive"))
    )
    (net (code "30") (name "/MDI3_N") (class "Default")
      (node (ref "T1") (pin "2") (pinfunction "PRI_2_2") (pintype "passive"))
      (node (ref "U5") (pin "14") (pinfunction "TXVN_D_14") (pintype "passive"))
    )
    (net (code "31") (name "/MDI3_P") (class "Default")
      (node (ref "T1") (pin "3") (pinfunction "PRI_3_3") (pintype "passive"))
      (node (ref "U5") (pin "13") (pinfunction "TXVP_D_13") (pintype "passive"))
    )
    (net (code "32") (name "/MDIA_N") (class "Default")
      (node (ref "J4") (pin "2") (pinfunction "BI_DA-_2") (pintype "passive"))
      (node (ref "T1") (pin "14") (pinfunction "SEC_2_14") (pintype "passive"))
    )
    (net (code "33") (name "/MDIA_P") (class "Default")
      (node (ref "J4") (pin "1") (pinfunction "BI_DA+_1") (pintype "passive"))
      (node (ref "T1") (pin "13") (pinfunction "SEC_1_13") (pintype "passive"))
    )
    (net (code "34") (name "/MDIB_N") (class "Default")
      (node (ref "J4") (pin "6") (pinfunction "BI_DB-_6") (pintype "passive"))
      (node (ref "T1") (pin "17") (pinfunction "SEC_5_17") (pintype "passive"))
    )
    (net (code "35") (name "/MDIB_P") (class "Default")
      (node (ref "J4") (pin "3") (pinfunction "BI_DB+_3") (pintype "passive"))
      (node (ref "T1") (pin "16") (pinfunction "SEC_4_16") (pintype "passive"))
    )
    (net (code "36") (name "/MDIC_N") (class "Default")
      (node (ref "J4") (pin "5") (pinfunction "BI_DC-_5") (pintype "passive"))
      (node (ref "T1") (pin "20") (pinfunction "SEC_8_20") (pintype "passive"))
    )
    (net (code "37") (name "/MDIC_P") (class "Default")
      (node (ref "J4") (pin "4") (pinfunction "BI_DC+_4") (pintype "passive"))
      (node (ref "T1") (pin "19") (pinfunction "SEC_7_19") (pintype "passive"))
    )
    (net (code "38") (name "/MDID_N") (class "Default")
      (node (ref "J4") (pin "8") (pinfunction "BI_DD-_8") (pintype "passive"))
      (node (ref "T1") (pin "23") (pinfunction "SEC_11_23") (pintype "passive"))
    )
    (net (code "39") (name "/MDID_P") (class "Default")
      (node (ref "J4") (pin "7") (pinfunction "BI_DD+_7") (pintype "passive"))
      (node (ref "T1") (pin "22") (pinfunction "SEC_10_22") (pintype "passive"))
    )
    (net (code "40") (name "/MUX1_CTRL") (class "Default")
      (node (ref "R6") (pin "1") (pinfunction "1_1") (pintype "passive"))
      (node (ref "S1") (pin "3") (pinfunction "COM_1_3") (pintype "passive"))
      (node (ref "U2") (pin "6") (pinfunction "S_6") (pintype "passive"))
    )
    (net (code "41") (name "/MUX2_CTRL") (class "Default")
      (node (ref "R7") (pin "1") (pinfunction "1_1") (pintype "passive"))
      (node (ref "S1") (pin "4") (pinfunction "COM_2_4") (pintype "passive"))
      (node (ref "U4") (pin "6") (pinfunction "S_6") (pintype "passive"))
    )
    (net (code "42") (name "/RESET_N") (class "Default")
      (node (ref "R19") (pin "1") (pinfunction "1_1") (pintype "passive"))
      (node (ref "U5") (pin "23") (pinfunction "HW_RSTN_23") (pintype "passive"))
    )
    (net (code "43") (name "/RF") (class "Default")
      (node (ref "C7") (pin "2") (pinfunction "2_2") (pintype "passive"))
      (node (ref "IC1") (pin "11") (pinfunction "RF_IN_11") (pintype "passive"))
      (node (ref "IC2") (pin "11") (pinfunction "RF_IN_11") (pintype "passive"))
    )
    (net (code "44") (name "/SPI_CLK") (class "Default")
      (node (ref "R35") (pin "2") (pinfunction "2_2") (pintype "passive"))
      (node (ref "U5") (pin "51") (pinfunction "SPI_CLK_51") (pintype "passive"))
      (node (ref "U7") (pin "6") (pinfunction "SCK_6") (pintype "input"))
    )
    (net (code "45") (name "/SPI_CS") (class "Default")
      (node (ref "R36") (pin "2") (pinfunction "2_2") (pintype "passive"))
      (node (ref "U5") (pin "50") (pinfunction "SPI_CS0_50") (pintype "passive"))
      (node (ref "U7") (pin "1") (pinfunction "~{CE}_1") (pintype "input"))
    )
    (net (code "46") (name "/SPI_DIO") (class "Default")
      (node (ref "R34") (pin "2") (pinfunction "2_2") (pintype "passive"))
      (node (ref "R39") (pin "2") (pinfunction "2_2") (pintype "passive"))
      (node (ref "U5") (pin "52") (pinfunction "SPI_DIO_52") (pintype "passive"))
      (node (ref "U7") (pin "5") (pinfunction "SI_5") (pintype "input"))
    )
    (net (code "47") (name "/SSRX_N") (class "Default")
      (node (ref "D5") (pin "2") (pinfunction "D-_2") (pintype "passive"))
      (node (ref "J6") (pin "A10") (pinfunction "SSRXn2_A10") (pintype "passive"))
      (node (ref "J6") (pin "B10") (pinfunction "SSRXn1_B10") (pintype "passive"))
      (node (ref "U5") (pin "44") (pinfunction "SSUSBRXN_44") (pintype "passive"))
    )
    (net (code "48") (name "/SSRX_P") (class "Default")
      (node (ref "D5") (pin "1") (pinfunction "D+_1") (pintype "passive"))
      (node (ref "J6") (pin "A11") (pinfunction "SSRXp2_A11") (pintype "passive"))
      (node (ref "J6") (pin "B11") (pinfunction "SSRXp1_B11") (pintype "passive"))
      (node (ref "U5") (pin "45") (pinfunction "SSUSBRXP_45") (pintype "passive"))
    )
    (net (code "49") (name "/SSTX_N") (class "Default")
      (node (ref "C9") (pin "2") (pinfunction "2_2") (pintype "passive"))
      (node (ref "D3") (pin "2") (pinfunction "D-_2") (pintype "passive"))
      (node (ref "U5") (pin "41") (pinfunction "SSUSB_TXN_41") (pintype "passive"))
    )
    (net (code "50") (name "/SSTX_P") (class "Default")
      (node (ref "C8") (pin "2") (pinfunction "2_2") (pintype "passive"))
      (node (ref "D3") (pin "1") (pinfunction "D+_1") (pintype "passive"))
      (node (ref "U5") (pin "42") (pinfunction "SSUSB_TXP_42") (pintype "passive"))
    )
    (net (code "51") (name "/USB3.0_SSTX_N") (class "Default")
      (node (ref "C9") (pin "1") (pinfunction "1_1") (pintype "passive"))
      (node (ref "J6") (pin "A3") (pinfunction "SSTXn1_A3") (pintype "passive"))
      (node (ref "J6") (pin "B3") (pinfunction "SSTXn2_B3") (pintype "passive"))
    )
    (net (code "52") (name "/USB3.0_SSTX_P") (class "Default")
      (node (ref "C8") (pin "1") (pinfunction "1_1") (pintype "passive"))
      (node (ref "J6") (pin "A2") (pinfunction "SSTXp1_A2") (pintype "passive"))
      (node (ref "J6") (pin "B2") (pinfunction "SSTXp2_B2") (pintype "passive"))
    )
    (net (code "53") (name "/VBUS") (class "Default")
      (node (ref "R17") (pin "1") (pinfunction "1_1") (pintype "passive"))
      (node (ref "R18") (pin "2") (pinfunction "2_2") (pintype "passive"))
      (node (ref "U5") (pin "34") (pinfunction "GPIO9(VBUS)_34") (pintype "passive"))
    )
    (net (code "54") (name "/VCORE_LDO") (class "Default")
      (node (ref "C21") (pin "2") (pinfunction "2_2") (pintype "passive"))
      (node (ref "FB1") (pin "1") (pinfunction "1_1") (pintype "passive"))
      (node (ref "U5") (pin "55") (pinfunction "VCORE_LDO_55") (pintype "passive"))
    )
    (net (code "55") (name "/XTL20N") (class "Default")
      (node (ref "R27") (pin "2") (pinfunction "2_2") (pintype "passive"))
      (node (ref "U5") (pin "16") (pinfunction "XTAL_XO_16") (pintype "passive"))
    )
    (net (code "56") (name "/XTL20P") (class "Default")
      (node (ref "R26") (pin "2") (pinfunction "2_2") (pintype "passive"))
      (node (ref "U5") (pin "17") (pinfunction "XTAL_IN_17") (pintype "passive"))
    )
    (net (code "57") (name "DVDD_33") (class "Default")
      (node (ref "C18") (pin "2") (pinfunction "2_2") (pintype "passive"))
      (node (ref "C20") (pin "2") (pinfunction "2_2") (pintype "passive"))
      (node (ref "C31") (pin "2") (pinfunction "2_2") (pintype "passive"))
      (node (ref "C32") (pin "2") (pinfunction "2_2") (pintype "passive"))
      (node (ref "C33") (pin "2") (pinfunction "2_2") (pintype "passive"))
      (node (ref "C34") (pin "2") (pinfunction "2_2") (pintype "passive"))
      (node (ref "FB4") (pin "1") (pinfunction "1_1") (pintype "passive"))
      (node (ref "FB5") (pin "1") (pinfunction "1_1") (pintype "passive"))
      (node (ref "L2") (pin "2") (pinfunction "2_2") (pintype "passive"))
      (node (ref "R10") (pin "2") (pinfunction "2_2") (pintype "passive"))
      (node (ref "R19") (pin "2") (pinfunction "2_2") (pintype "passive"))
      (node (ref "R22") (pin "2") (pinfunction "2_2") (pintype "passive"))
      (node (ref "R24") (pin "2") (pinfunction "2_2") (pintype "passive"))
      (node (ref "R25") (pin "2") (pinfunction "2_2") (pintype "passive"))
      (node (ref "R31") (pin "1") (pinfunction "1_1") (pintype "passive"))
      (node (ref "R32") (pin "1") (pinfunction "1_1") (pintype "passive"))
      (node (ref "R34") (pin "1") (pinfunction "1_1") (pintype "passive"))
      (node (ref "R35") (pin "1") (pinfunction "1_1") (pintype "passive"))
      (node (ref "R36") (pin "1") (pinfunction "1_1") (pintype "passive"))
      (node (ref "R37") (pin "1") (pinfunction "1_1") (pintype "passive"))
      (node (ref "R38") (pin "1") (pinfunction "1_1") (pintype "passive"))
      (node (ref "R8") (pin "2") (pinfunction "2_2") (pintype "passive"))
      (node (ref "U5") (pin "25") (pinfunction "DVDD33_25") (pintype "passive"))
      (node (ref "U5") (pin "36") (pinfunction "DVDD33_36") (pintype "passive"))
      (node (ref "U5") (pin "54") (pinfunction "AVDD33_LDO_54") (pintype "passive"))
      (node (ref "U5") (pin "59") (pinfunction "AVD33_BUCK_59") (pintype "passive"))
      (node (ref "U6") (pin "1") (pinfunction "VO/VFB_1") (pintype "bidirectional"))
      (node (ref "U7") (pin "8") (pinfunction "VDD_8") (pintype "power_in"))
    )
    (net (code "58") (name "GND") (class "Default")
      (node (ref "C1") (pin "1") (pinfunction "1_1") (pintype "passive"))
      (node (ref "C10") (pin "1") (pinfunction "1_1") (pintype "passive"))
      (node (ref "C11") (pin "1") (pinfunction "1_1") (pintype "passive"))
      (node (ref "C12") (pin "1") (pinfunction "1_1") (pintype "passive"))
      (node (ref "C13") (pin "1") (pinfunction "1_1") (pintype "passive"))
      (node (ref "C14") (pin "1") (pinfunction "1_1") (pintype "passive"))
      (node (ref "C15") (pin "1") (pinfunction "1_1") (pintype "passive"))
      (node (ref "C16") (pin "1") (pinfunction "1_1") (pintype "passive"))
      (node (ref "C17") (pin "1") (pinfunction "1_1") (pintype "passive"))
      (node (ref "C18") (pin "1") (pinfunction "1_1") (pintype "passive"))
      (node (ref "C19") (pin "1") (pinfunction "1_1") (pintype "passive"))
      (node (ref "C2") (pin "1") (pinfunction "1_1") (pintype "passive"))
      (node (ref "C20") (pin "1") (pinfunction "1_1") (pintype "passive"))
      (node (ref "C21") (pin "1") (pinfunction "1_1") (pintype "passive"))
      (node (ref "C22") (pin "1") (pinfunction "1_1") (pintype "passive"))
      (node (ref "C23") (pin "1") (pinfunction "1_1") (pintype "passive"))
      (node (ref "C24") (pin "1") (pinfunction "1_1") (pintype "passive"))
      (node (ref "C25") (pin "1") (pinfunction "1_1") (pintype "passive"))
      (node (ref "C26") (pin "1") (pinfunction "1_1") (pintype "passive"))
      (node (ref "C27") (pin "1") (pinfunction "1_1") (pintype "passive"))
      (node (ref "C28") (pin "1") (pinfunction "1_1") (pintype "passive"))
      (node (ref "C29") (pin "1") (pinfunction "1_1") (pintype "passive"))
      (node (ref "C3") (pin "1") (pinfunction "1_1") (pintype "passive"))
      (node (ref "C30") (pin "1") (pinfunction "1_1") (pintype "passive"))
      (node (ref "C31") (pin "1") (pinfunction "1_1") (pintype "passive"))
      (node (ref "C32") (pin "1") (pinfunction "1_1") (pintype "passive"))
      (node (ref "C33") (pin "1") (pinfunction "1_1") (pintype "passive"))
      (node (ref "C34") (pin "1") (pinfunction "1_1") (pintype "passive"))
      (node (ref "C35") (pin "1") (pinfunction "1_1") (pintype "passive"))
      (node (ref "C36") (pin "1") (pinfunction "1_1") (pintype "passive"))
      (node (ref "C37") (pin "1") (pinfunction "1_1") (pintype "passive"))
      (node (ref "C38") (pin "1") (pinfunction "1_1") (pintype "passive"))
      (node (ref "C39") (pin "1") (pinfunction "1_1") (pintype "passive"))
      (node (ref "C4") (pin "1") (pinfunction "1_1") (pintype "passive"))
      (node (ref "C40") (pin "1") (pinfunction "1_1") (pintype "passive"))
      (node (ref "C41") (pin "1") (pinfunction "1_1") (pintype "passive"))
      (node (ref "C42") (pin "1") (pinfunction "1_1") (pintype "passive"))
      (node (ref "C43") (pin "1") (pinfunction "1_1") (pintype "passive"))
      (node (ref "C44") (pin "1") (pinfunction "1_1") (pintype "passive"))
      (node (ref "C45") (pin "2") (pinfunction "2_2") (pintype "passive"))
      (node (ref "C46") (pin "2") (pinfunction "2_2") (pintype "passive"))
      (node (ref "C48") (pin "2") (pinfunction "2_2") (pintype "passive"))
      (node (ref "C49") (pin "2") (pinfunction "2_2") (pintype "passive"))
      (node (ref "C5") (pin "1") (pinfunction "1_1") (pintype "passive"))
      (node (ref "C50") (pin "2") (pinfunction "2_2") (pintype "passive"))
      (node (ref "C51") (pin "2") (pinfunction "2_2") (pintype "passive"))
      (node (ref "C6") (pin "2") (pinfunction "2_2") (pintype "passive"))
      (node (ref "D3") (pin "3") (pinfunction "GND_3") (pintype "passive"))
      (node (ref "D4") (pin "3") (pinfunction "GND_3") (pintype "passive"))
      (node (ref "D5") (pin "3") (pinfunction "GND_3") (pintype "passive"))
      (node (ref "IC1") (pin "10") (pinfunction "GND_1_10") (pintype "passive"))
      (node (ref "IC1") (pin "12") (pinfunction "GND_2_12") (pintype "passive"))
      (node (ref "IC1") (pin "13") (pinfunction "GND_3_13") (pintype "passive"))
      (node (ref "IC1") (pin "24") (pinfunction "GND_4_24") (pintype "passive"))
      (node (ref "IC1") (pin "7") (pinfunction "V_USB_7") (pintype "passive"))
      (node (ref "IC2") (pin "1") (pinfunction "GND_1_1") (pintype "passive"))
      (node (ref "IC2") (pin "10") (pinfunction "GND_2_10") (pintype "passive"))
      (node (ref "IC2") (pin "12") (pinfunction "GND_3_12") (pintype "passive"))
      (node (ref "J1") (pin "2") (pinfunction "2_2") (pintype "passive"))
      (node (ref "J1") (pin "3") (pinfunction "3_3") (pintype "passive"))
      (node (ref "J1") (pin "4") (pinfunction "4_4") (pintype "passive"))
      (node (ref "J1") (pin "5") (pinfunction "5_5") (pintype "passive"))
      (node (ref "J2") (pin "2") (pinfunction "2_2") (pintype "passive"))
      (node (ref "J2") (pin "3") (pinfunction "3_3") (pintype "passive"))
      (node (ref "J2") (pin "4") (pinfunction "4_4") (pintype "passive"))
      (node (ref "J2") (pin "5") (pinfunction "5_5") (pintype "passive"))
      (node (ref "J3") (pin "1") (pinfunction "1_1") (pintype "passive"))
      (node (ref "J5") (pin "2") (pinfunction "2_2") (pintype "passive"))
      (node (ref "J5") (pin "3") (pinfunction "3_3") (pintype "passive"))
      (node (ref "J5") (pin "4") (pinfunction "4_4") (pintype "passive"))
      (node (ref "J5") (pin "5") (pinfunction "5_5") (pintype "passive"))
      (node (ref "J6") (pin "A1") (pinfunction "GND_A1") (pintype "passive"))
      (node (ref "J6") (pin "A12") (pinfunction "GND_A12") (pintype "passive"))
      (node (ref "J6") (pin "B1") (pinfunction "GND_B1") (pintype "passive"))
      (node (ref "J6") (pin "B12") (pinfunction "GND_B12") (pintype "passive"))
      (node (ref "R1") (pin "2") (pinfunction "2_2") (pintype "passive"))
      (node (ref "R15") (pin "2") (pinfunction "2_2") (pintype "passive"))
      (node (ref "R16") (pin "2") (pinfunction "2_2") (pintype "passive"))
      (node (ref "R18") (pin "1") (pinfunction "1_1") (pintype "passive"))
      (node (ref "R21") (pin "1") (pinfunction "1_1") (pintype "passive"))
      (node (ref "R29") (pin "2") (pinfunction "2_2") (pintype "passive"))
      (node (ref "R30") (pin "2") (pinfunction "2_2") (pintype "passive"))
      (node (ref "R33") (pin "1") (pinfunction "1_1") (pintype "passive"))
      (node (ref "R4") (pin "1") (pinfunction "1_1") (pintype "passive"))
      (node (ref "R41") (pin "2") (pinfunction "2_2") (pintype "passive"))
      (node (ref "S1") (pin "1") (pinfunction "NO_1_1") (pintype "passive"))
      (node (ref "S1") (pin "2") (pinfunction "NO_2_2") (pintype "passive"))
      (node (ref "U1") (pin "4") (pinfunction "GND_4") (pintype "passive"))
      (node (ref "U2") (pin "2") (pinfunction "GND_2") (pintype "passive"))
      (node (ref "U3") (pin "4") (pinfunction "GND_4") (pintype "passive"))
      (node (ref "U4") (pin "2") (pinfunction "GND_2") (pintype "passive"))
      (node (ref "U5") (pin "1") (pinfunction "AVSS33_BUCK_1") (pintype "passive"))
      (node (ref "U5") (pin "2") (pinfunction "AVSS33_BUCK_2") (pintype "passive"))
      (node (ref "U5") (pin "61") (pinfunction "E_PAD_61") (pintype "passive"))
      (node (ref "U6") (pin "2") (pinfunction "GND_2") (pintype "power_in"))
      (node (ref "U6") (pin "7") (pinfunction "Thermal_Pad_7") (pintype "power_in"))
      (node (ref "U7") (pin "4") (pinfunction "VSS_4") (pintype "power_in"))
      (node (ref "U7") (pin "9") (pinfunction "VSS_9") (pintype "power_in"))
      (node (ref "U8") (pin "2") (pinfunction "GND_2") (pintype "power_in"))
      (node (ref "U8") (pin "7") (pinfunction "Thermal_Pad_7") (pintype "power_in"))
      (node (ref "Y1") (pin "2") (pinfunction "GND_2") (pintype "passive"))
      (node (ref "Y1") (pin "4") (pinfunction "GND_4") (pintype "passive"))
    )
    (net (code "59") (name "Net-(C5-Pad2)") (class "Default")
      (node (ref "C5") (pin "2") (pinfunction "2_2") (pintype "passive"))
      (node (ref "L1") (pin "1") (pinfunction "1_1") (pintype "passive"))
      (node (ref "R12") (pin "2") (pinfunction "2_2") (pintype "passive"))
    )
    (net (code "60") (name "Net-(C13-Pad2)") (class "Default")
      (node (ref "C13") (pin "2") (pinfunction "2_2") (pintype "passive"))
      (node (ref "R26") (pin "1") (pinfunction "1_1") (pintype "passive"))
      (node (ref "Y1") (pin "1") (pinfunction "1_1") (pintype "passive"))
    )
    (net (code "61") (name "Net-(C14-Pad2)") (class "Default")
      (node (ref "C14") (pin "2") (pinfunction "2_2") (pintype "passive"))
      (node (ref "R27") (pin "1") (pinfunction "1_1") (pintype "passive"))
      (node (ref "Y1") (pin "3") (pinfunction "3_3") (pintype "passive"))
    )
    (net (code "62") (name "Net-(C47-Pad2)") (class "Default")
      (node (ref "C47") (pin "2") (pinfunction "2_2") (pintype "passive"))
      (node (ref "R20") (pin "2") (pinfunction "2_2") (pintype "passive"))
      (node (ref "R42") (pin "2") (pinfunction "2_2") (pintype "passive"))
      (node (ref "R43") (pin "2") (pinfunction "2_2") (pintype "passive"))
      (node (ref "R44") (pin "2") (pinfunction "2_2") (pintype "passive"))
      (node (ref "R45") (pin "2") (pinfunction "2_2") (pintype "passive"))
    )
    (net (code "63") (name "Net-(D1-PadA)") (class "Default")
      (node (ref "D1") (pin "A") (pinfunction "A_A") (pintype "passive"))
      (node (ref "R2") (pin "1") (pinfunction "1_1") (pintype "passive"))
    )
    (net (code "64") (name "Net-(D2-PadA)") (class "Default")
      (node (ref "D2") (pin "A") (pinfunction "A_A") (pintype "passive"))
      (node (ref "R5") (pin "1") (pinfunction "1_1") (pintype "passive"))
    )
    (net (code "65") (name "Net-(J4-A_GR)") (class "Default")
      (node (ref "J4") (pin "11") (pinfunction "A_GR_11") (pintype "passive"))
      (node (ref "R10") (pin "1") (pinfunction "1_1") (pintype "passive"))
    )
    (net (code "66") (name "Net-(J4-A_YEL)") (class "Default")
      (node (ref "J4") (pin "9") (pinfunction "A_YEL_9") (pintype "passive"))
      (node (ref "R8") (pin "1") (pinfunction "1_1") (pintype "passive"))
    )
    (net (code "67") (name "Net-(J6-CC1)") (class "Default")
      (node (ref "J6") (pin "A5") (pinfunction "CC1_A5") (pintype "passive"))
      (node (ref "R29") (pin "1") (pinfunction "1_1") (pintype "passive"))
    )
    (net (code "68") (name "Net-(J6-CC2)") (class "Default")
      (node (ref "J6") (pin "B5") (pinfunction "CC2_B5") (pintype "passive"))
      (node (ref "R30") (pin "1") (pinfunction "1_1") (pintype "passive"))
    )
    (net (code "69") (name "Net-(J6-Shield)") (class "Default")
      (node (ref "C15") (pin "2") (pinfunction "2_2") (pintype "passive"))
      (node (ref "J6") (pin "S") (pinfunction "Shield_S") (pintype "passive"))
      (node (ref "R33") (pin "2") (pinfunction "2_2") (pintype "passive"))
    )
    (net (code "70") (name "Net-(Q1-G)") (class "Default")
      (node (ref "Q1") (pin "1") (pinfunction "G_1") (pintype "passive"))
      (node (ref "R13") (pin "1") (pinfunction "1_1") (pintype "passive"))
      (node (ref "R14") (pin "2") (pinfunction "2_2") (pintype "passive"))
      (node (ref "R16") (pin "1") (pinfunction "1_1") (pintype "passive"))
    )
    (net (code "71") (name "Net-(Q1-S)") (class "Default")
      (node (ref "Q1") (pin "2") (pinfunction "S_2") (pintype "passive"))
      (node (ref "R12") (pin "1") (pinfunction "1_1") (pintype "passive"))
    )
    (net (code "72") (name "Net-(T1-PRI_1)") (class "Default")
      (node (ref "C48") (pin "1") (pinfunction "1_1") (pintype "passive"))
      (node (ref "T1") (pin "1") (pinfunction "PRI_1_1") (pintype "passive"))
    )
    (net (code "73") (name "Net-(T1-PRI_4)") (class "Default")
      (node (ref "C49") (pin "1") (pinfunction "1_1") (pintype "passive"))
      (node (ref "T1") (pin "4") (pinfunction "PRI_4_4") (pintype "passive"))
    )
    (net (code "74") (name "Net-(T1-PRI_7)") (class "Default")
      (node (ref "C50") (pin "1") (pinfunction "1_1") (pintype "passive"))
      (node (ref "T1") (pin "7") (pinfunction "PRI_7_7") (pintype "passive"))
    )
    (net (code "75") (name "Net-(T1-PRI_10)") (class "Default")
      (node (ref "C51") (pin "1") (pinfunction "1_1") (pintype "passive"))
      (node (ref "T1") (pin "10") (pinfunction "PRI_10_10") (pintype "passive"))
    )
    (net (code "76") (name "Net-(T1-SEC_3)") (class "Default")
      (node (ref "R44") (pin "1") (pinfunction "1_1") (pintype "passive"))
      (node (ref "T1") (pin "15") (pinfunction "SEC_3_15") (pintype "passive"))
    )
    (net (code "77") (name "Net-(T1-SEC_6)") (class "Default")
      (node (ref "R43") (pin "1") (pinfunction "1_1") (pintype "passive"))
      (node (ref "T1") (pin "18") (pinfunction "SEC_6_18") (pintype "passive"))
    )
    (net (code "78") (name "Net-(T1-SEC_9)") (class "Default")
      (node (ref "R42") (pin "1") (pinfunction "1_1") (pintype "passive"))
      (node (ref "T1") (pin "21") (pinfunction "SEC_9_21") (pintype "passive"))
    )
    (net (code "79") (name "Net-(T1-SEC_12)") (class "Default")
      (node (ref "R20") (pin "1") (pinfunction "1_1") (pintype "passive"))
      (node (ref "T1") (pin "24") (pinfunction "SEC_12_24") (pintype "passive"))
    )
    (net (code "80") (name "Net-(U1-~{OE1})") (class "Default")
      (node (ref "R1") (pin "1") (pinfunction "1_1") (pintype "passive"))
      (node (ref "U1") (pin "1") (pinfunction "~{OE1}_1") (pintype "passive"))
      (node (ref "U1") (pin "7") (pinfunction "~{OE2}_7") (pintype "passive"))
    )
    (net (code "81") (name "Net-(U3-~{OE1})") (class "Default")
      (node (ref "R4") (pin "2") (pinfunction "2_2") (pintype "passive"))
      (node (ref "U3") (pin "1") (pinfunction "~{OE1}_1") (pintype "passive"))
      (node (ref "U3") (pin "7") (pinfunction "~{OE2}_7") (pintype "passive"))
    )
    (net (code "82") (name "Net-(U4-B2)") (class "Default")
      (node (ref "J2") (pin "1") (pinfunction "1_1") (pintype "passive"))
      (node (ref "U4") (pin "1") (pinfunction "B2_1") (pintype "passive"))
    )
    (net (code "83") (name "Net-(U5-AVDD18_XTAL)") (class "Default")
      (node (ref "C28") (pin "2") (pinfunction "2_2") (pintype "passive"))
      (node (ref "C29") (pin "2") (pinfunction "2_2") (pintype "passive"))
      (node (ref "FB3") (pin "1") (pinfunction "1_1") (pintype "passive"))
      (node (ref "U5") (pin "15") (pinfunction "AVDD18_XTAL_15") (pintype "passive"))
    )
    (net (code "84") (name "Net-(U5-GPIO3(LED2))") (class "Default")
      (node (ref "R22") (pin "1") (pinfunction "1_1") (pintype "passive"))
      (node (ref "U5") (pin "29") (pinfunction "GPIO3(LED2)_29") (pintype "passive"))
    )
    (net (code "85") (name "Net-(U5-GPIO8(WAKEUP_B))") (class "Default")
      (node (ref "R25") (pin "1") (pinfunction "1_1") (pintype "passive"))
      (node (ref "U5") (pin "33") (pinfunction "GPIO8(WAKEUP_B)_33") (pintype "passive"))
    )
    (net (code "86") (name "Net-(U5-GPIO10(SYNCE_LOCK))") (class "Default")
      (node (ref "R24") (pin "1") (pinfunction "1_1") (pintype "passive"))
      (node (ref "U5") (pin "19") (pinfunction "GPIO10(SYNCE_LOCK)_19") (pintype "passive"))
    )
    (net (code "87") (name "Net-(U5-MPXP)") (class "Default")
      (node (ref "R21") (pin "2") (pinfunction "2_2") (pintype "passive"))
      (node (ref "U5") (pin "9") (pinfunction "MPXP_9") (pintype "passive"))
    )
    (net (code "88") (name "Net-(U6-SW)") (class "Default")
      (node (ref "L2") (pin "1") (pinfunction "1_1") (pintype "passive"))
      (node (ref "U6") (pin "3") (pinfunction "SW_3") (pintype "passive"))
    )
    (net (code "89") (name "Net-(U7-SO)") (class "Default")
      (node (ref "R39") (pin "1") (pinfunction "1_1") (pintype "passive"))
      (node (ref "U7") (pin "2") (pinfunction "SO_2") (pintype "output"))
    )
    (net (code "90") (name "Net-(U7-~{HOLD})") (class "Default")
      (node (ref "R37") (pin "2") (pinfunction "2_2") (pintype "passive"))
      (node (ref "U7") (pin "7") (pinfunction "~{HOLD}_7") (pintype "input"))
    )
    (net (code "91") (name "Net-(U7-~{WP})") (class "Default")
      (node (ref "R38") (pin "2") (pinfunction "2_2") (pintype "passive"))
      (node (ref "U7") (pin "3") (pinfunction "~{WP}_3") (pintype "input"))
    )
    (net (code "92") (name "Net-(U8-SW)") (class "Default")
      (node (ref "L3") (pin "1") (pinfunction "1_1") (pintype "passive"))
      (node (ref "U8") (pin "3") (pinfunction "SW_3") (pintype "passive"))
    )
    (net (code "93") (name "Net-(U8-VO{slash}VFB)") (class "Default")
      (node (ref "R40") (pin "2") (pinfunction "2_2") (pintype "passive"))
      (node (ref "R41") (pin "1") (pinfunction "1_1") (pintype "passive"))
      (node (ref "U8") (pin "1") (pinfunction "VO/VFB_1") (pintype "bidirectional"))
    )
    (net (code "94") (name "PE") (class "Default")
      (node (ref "C45") (pin "1") (pinfunction "1_1") (pintype "passive"))
      (node (ref "C46") (pin "1") (pinfunction "1_1") (pintype "passive"))
      (node (ref "C47") (pin "1") (pinfunction "1_1") (pintype "passive"))
      (node (ref "C6") (pin "1") (pinfunction "1_1") (pintype "passive"))
      (node (ref "J4") (pin "MH1") (pinfunction "MH1_MH1") (pintype "passive"))
      (node (ref "J4") (pin "MH2") (pinfunction "MH2_MH2") (pintype "passive"))
      (node (ref "R15") (pin "1") (pinfunction "1_1") (pintype "passive"))
      (node (ref "R45") (pin "1") (pinfunction "1_1") (pintype "passive"))
    )
    (net (code "95") (name "VBUS_+5V") (class "Default")
      (node (ref "C1") (pin "2") (pinfunction "2_2") (pintype "passive"))
      (node (ref "C19") (pin "2") (pinfunction "2_2") (pintype "passive"))
      (node (ref "C2") (pin "2") (pinfunction "2_2") (pintype "passive"))
      (node (ref "C3") (pin "2") (pinfunction "2_2") (pintype "passive"))
      (node (ref "C4") (pin "2") (pinfunction "2_2") (pintype "passive"))
      (node (ref "C40") (pin "2") (pinfunction "2_2") (pintype "passive"))
      (node (ref "J3") (pin "2") (pinfunction "2_2") (pintype "passive"))
      (node (ref "J6") (pin "A4") (pinfunction "VBUS_A4") (pintype "passive"))
      (node (ref "J6") (pin "A9") (pinfunction "VBUS_A9") (pintype "passive"))
      (node (ref "J6") (pin "B4") (pinfunction "VBUS_B4") (pintype "passive"))
      (node (ref "J6") (pin "B9") (pinfunction "VBUS_B9") (pintype "passive"))
      (node (ref "R11") (pin "2") (pinfunction "2_2") (pintype "passive"))
      (node (ref "R17") (pin "2") (pinfunction "2_2") (pintype "passive"))
      (node (ref "R2") (pin "2") (pinfunction "2_2") (pintype "passive"))
      (node (ref "R5") (pin "2") (pinfunction "2_2") (pintype "passive"))
      (node (ref "R6") (pin "2") (pinfunction "2_2") (pintype "passive"))
      (node (ref "R7") (pin "2") (pinfunction "2_2") (pintype "passive"))
      (node (ref "U1") (pin "8") (pinfunction "VCC_8") (pintype "passive"))
      (node (ref "U2") (pin "5") (pinfunction "VCC_5") (pintype "passive"))
      (node (ref "U3") (pin "8") (pinfunction "VCC_8") (pintype "passive"))
      (node (ref "U4") (pin "5") (pinfunction "VCC_5") (pintype "passive"))
      (node (ref "U6") (pin "4") (pinfunction "VIN_SW_4") (pintype "input"))
      (node (ref "U6") (pin "5") (pinfunction "VIN_A_5") (pintype "input"))
      (node (ref "U6") (pin "6") (pinfunction "VINH_6") (pintype "input"))
      (node (ref "U8") (pin "4") (pinfunction "VIN_SW_4") (pintype "input"))
      (node (ref "U8") (pin "5") (pinfunction "VIN_A_5") (pintype "input"))
      (node (ref "U8") (pin "6") (pinfunction "VINH_6") (pintype "input"))
    )
    (net (code "96") (name "VCCK10") (class "Default")
      (node (ref "C30") (pin "2") (pinfunction "2_2") (pintype "passive"))
      (node (ref "C41") (pin "2") (pinfunction "2_2") (pintype "passive"))
      (node (ref "C42") (pin "2") (pinfunction "2_2") (pintype "passive"))
      (node (ref "C43") (pin "2") (pinfunction "2_2") (pintype "passive"))
      (node (ref "C44") (pin "2") (pinfunction "2_2") (pintype "passive"))
      (node (ref "L3") (pin "2") (pinfunction "2_2") (pintype "passive"))
      (node (ref "R40") (pin "1") (pinfunction "1_1") (pintype "passive"))
      (node (ref "U5") (pin "24") (pinfunction "VCCK_24") (pintype "passive"))
      (node (ref "U5") (pin "30") (pinfunction "VCCK_30") (pintype "passive"))
      (node (ref "U5") (pin "31") (pinfunction "VCCK_31") (pintype "passive"))
      (node (ref "U5") (pin "32") (pinfunction "VCCK_32") (pintype "passive"))
      (node (ref "U5") (pin "57") (pinfunction "VCCK_57") (pintype "passive"))
      (node (ref "U5") (pin "58") (pinfunction "VCCK_58") (pintype "passive"))
    )
    (net (code "97") (name "VDD_NEO") (class "Default")
      (node (ref "C10") (pin "2") (pinfunction "2_2") (pintype "passive"))
      (node (ref "C11") (pin "2") (pinfunction "2_2") (pintype "passive"))
      (node (ref "C12") (pin "2") (pinfunction "2_2") (pintype "passive"))
      (node (ref "FB5") (pin "2") (pinfunction "2_2") (pintype "passive"))
      (node (ref "IC1") (pin "2") (pinfunction "D_SEL_2") (pintype "passive"))
      (node (ref "IC1") (pin "22") (pinfunction "V_BCKP_22") (pintype "passive"))
      (node (ref "IC1") (pin "23") (pinfunction "VCC_23") (pintype "passive"))
      (node (ref "IC2") (pin "6") (pinfunction "V_BCKP_6") (pintype "passive"))
      (node (ref "IC2") (pin "8") (pinfunction "VCC_8") (pintype "passive"))
    )
    (net (code "98") (name "unconnected-(IC1-EXTINT-Pad4)") (class "Default")
      (node (ref "IC1") (pin "4") (pinfunction "EXTINT_4") (pintype "passive+no_connect"))
    )
    (net (code "99") (name "unconnected-(IC1-RESERVED_1-Pad15)") (class "Default")
      (node (ref "IC1") (pin "15") (pinfunction "RESERVED_1_15") (pintype "passive+no_connect"))
    )
    (net (code "100") (name "unconnected-(IC1-RESERVED_2-Pad16)") (class "Default")
      (node (ref "IC1") (pin "16") (pinfunction "RESERVED_2_16") (pintype "passive+no_connect"))
    )
    (net (code "101") (name "unconnected-(IC1-RESERVED_3-Pad17)") (class "Default")
      (node (ref "IC1") (pin "17") (pinfunction "RESERVED_3_17") (pintype "passive+no_connect"))
    )
    (net (code "102") (name "unconnected-(IC1-RESET_N-Pad8)") (class "Default")
      (node (ref "IC1") (pin "8") (pinfunction "RESET_N_8") (pintype "passive+no_connect"))
    )
    (net (code "103") (name "unconnected-(IC1-SAFEBOOT_N-Pad1)") (class "Default")
      (node (ref "IC1") (pin "1") (pinfunction "SAFEBOOT_N_1") (pintype "passive+no_connect"))
    )
    (net (code "104") (name "unconnected-(IC1-SCL_{slash}_SPI_SLK_-Pad19)") (class "Default")
      (node (ref "IC1") (pin "19") (pinfunction "SCL_/_SPI_SLK__19") (pintype "passive"))
    )
    (net (code "105") (name "unconnected-(IC1-SDA_{slash}_SPI_CS_N-Pad18)") (class "Default")
      (node (ref "IC1") (pin "18") (pinfunction "SDA_/_SPI_CS_N_18") (pintype "passive"))
    )
    (net (code "106") (name "unconnected-(IC1-USB_DM-Pad5)") (class "Default")
      (node (ref "IC1") (pin "5") (pinfunction "USB_DM_5") (pintype "passive+no_connect"))
    )
    (net (code "107") (name "unconnected-(IC1-USB_DP-Pad6)") (class "Default")
      (node (ref "IC1") (pin "6") (pinfunction "USB_DP_6") (pintype "passive+no_connect"))
    )
    (net (code "108") (name "unconnected-(IC1-VCC_RF-Pad9)") (class "Default")
      (node (ref "IC1") (pin "9") (pinfunction "VCC_RF_9") (pintype "passive+no_connect"))
    )
    (net (code "109") (name "unconnected-(IC2-EXTINT-Pad5)") (class "Default")
      (node (ref "IC2") (pin "5") (pinfunction "EXTINT_5") (pintype "passive+no_connect"))
    )
    (net (code "110") (name "unconnected-(IC2-RESET_N-Pad9)") (class "Default")
      (node (ref "IC2") (pin "9") (pinfunction "RESET_N_9") (pintype "passive+no_connect"))
    )
    (net (code "111") (name "unconnected-(IC2-SAFEBOOT_N-Pad18)") (class "Default")
      (node (ref "IC2") (pin "18") (pinfunction "SAFEBOOT_N_18") (pintype "passive+no_connect"))
    )
    (net (code "112") (name "unconnected-(IC2-SCL-Pad17)") (class "Default")
      (node (ref "IC2") (pin "17") (pinfunction "SCL_17") (pintype "passive+no_connect"))
    )
    (net (code "113") (name "unconnected-(IC2-SDA-Pad16)") (class "Default")
      (node (ref "IC2") (pin "16") (pinfunction "SDA_16") (pintype "passive+no_connect"))
    )
    (net (code "114") (name "unconnected-(IC2-VCC_RF-Pad14)") (class "Default")
      (node (ref "IC2") (pin "14") (pinfunction "VCC_RF_14") (pintype "passive+no_connect"))
    )
    (net (code "115") (name "unconnected-(IC2-VIO_SEL-Pad15)") (class "Default")
      (node (ref "IC2") (pin "15") (pinfunction "VIO_SEL_15") (pintype "passive"))
    )
    (net (code "116") (name "unconnected-(IC2-V_IO-Pad7)") (class "Default")
      (node (ref "IC2") (pin "7") (pinfunction "V_IO_7") (pintype "passive"))
    )
    (net (code "117") (name "unconnected-(J6-SBU1-PadA8)") (class "Default")
      (node (ref "J6") (pin "A8") (pinfunction "SBU1_A8") (pintype "passive+no_connect"))
    )
    (net (code "118") (name "unconnected-(J6-SBU2-PadB8)") (class "Default")
      (node (ref "J6") (pin "B8") (pinfunction "SBU2_B8") (pintype "passive+no_connect"))
    )
    (net (code "119") (name "unconnected-(U5-CKO-Pad18)") (class "Default")
      (node (ref "U5") (pin "18") (pinfunction "CKO_18") (pintype "passive+no_connect"))
    )
    (net (code "120") (name "unconnected-(U5-GPIO0(MDC)-Pad48)") (class "Default")
      (node (ref "U5") (pin "48") (pinfunction "GPIO0(MDC)_48") (pintype "passive+no_connect"))
    )
    (net (code "121") (name "unconnected-(U5-GPIO1(MDIO)-Pad49)") (class "Default")
      (node (ref "U5") (pin "49") (pinfunction "GPIO1(MDIO)_49") (pintype "passive+no_connect"))
    )
    (net (code "122") (name "unconnected-(U5-GPIO2-Pad22)") (class "Default")
      (node (ref "U5") (pin "22") (pinfunction "GPIO2_22") (pintype "passive+no_connect"))
    )
    (net (code "123") (name "unconnected-(U5-GPIO15(1588_TOD)-Pad47)") (class "Default")
      (node (ref "U5") (pin "47") (pinfunction "GPIO15(1588_TOD)_47") (pintype "passive+no_connect"))
    )
    (net (code "124") (name "unconnected-(U5-LX-Pad60)") (class "Default")
      (node (ref "U5") (pin "60") (pinfunction "LX_60") (pintype "passive+no_connect"))
    )
  )
)
